# Titan_v1p3.net
KiCad netlist of a schematic drawn in EAGLE
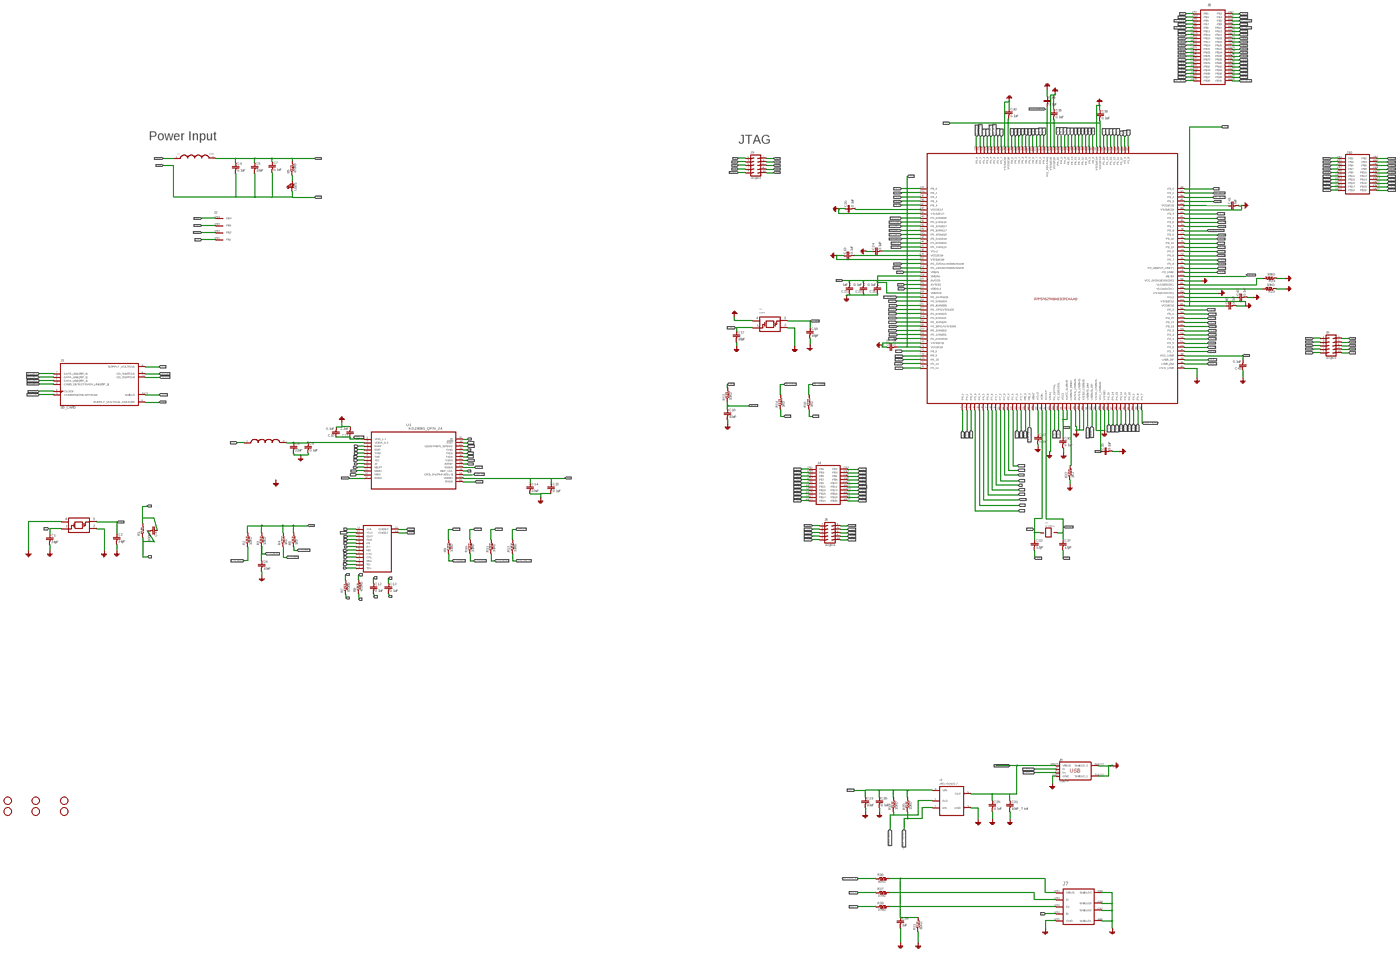
[diagram p0: schematic, sheet 1, overview]
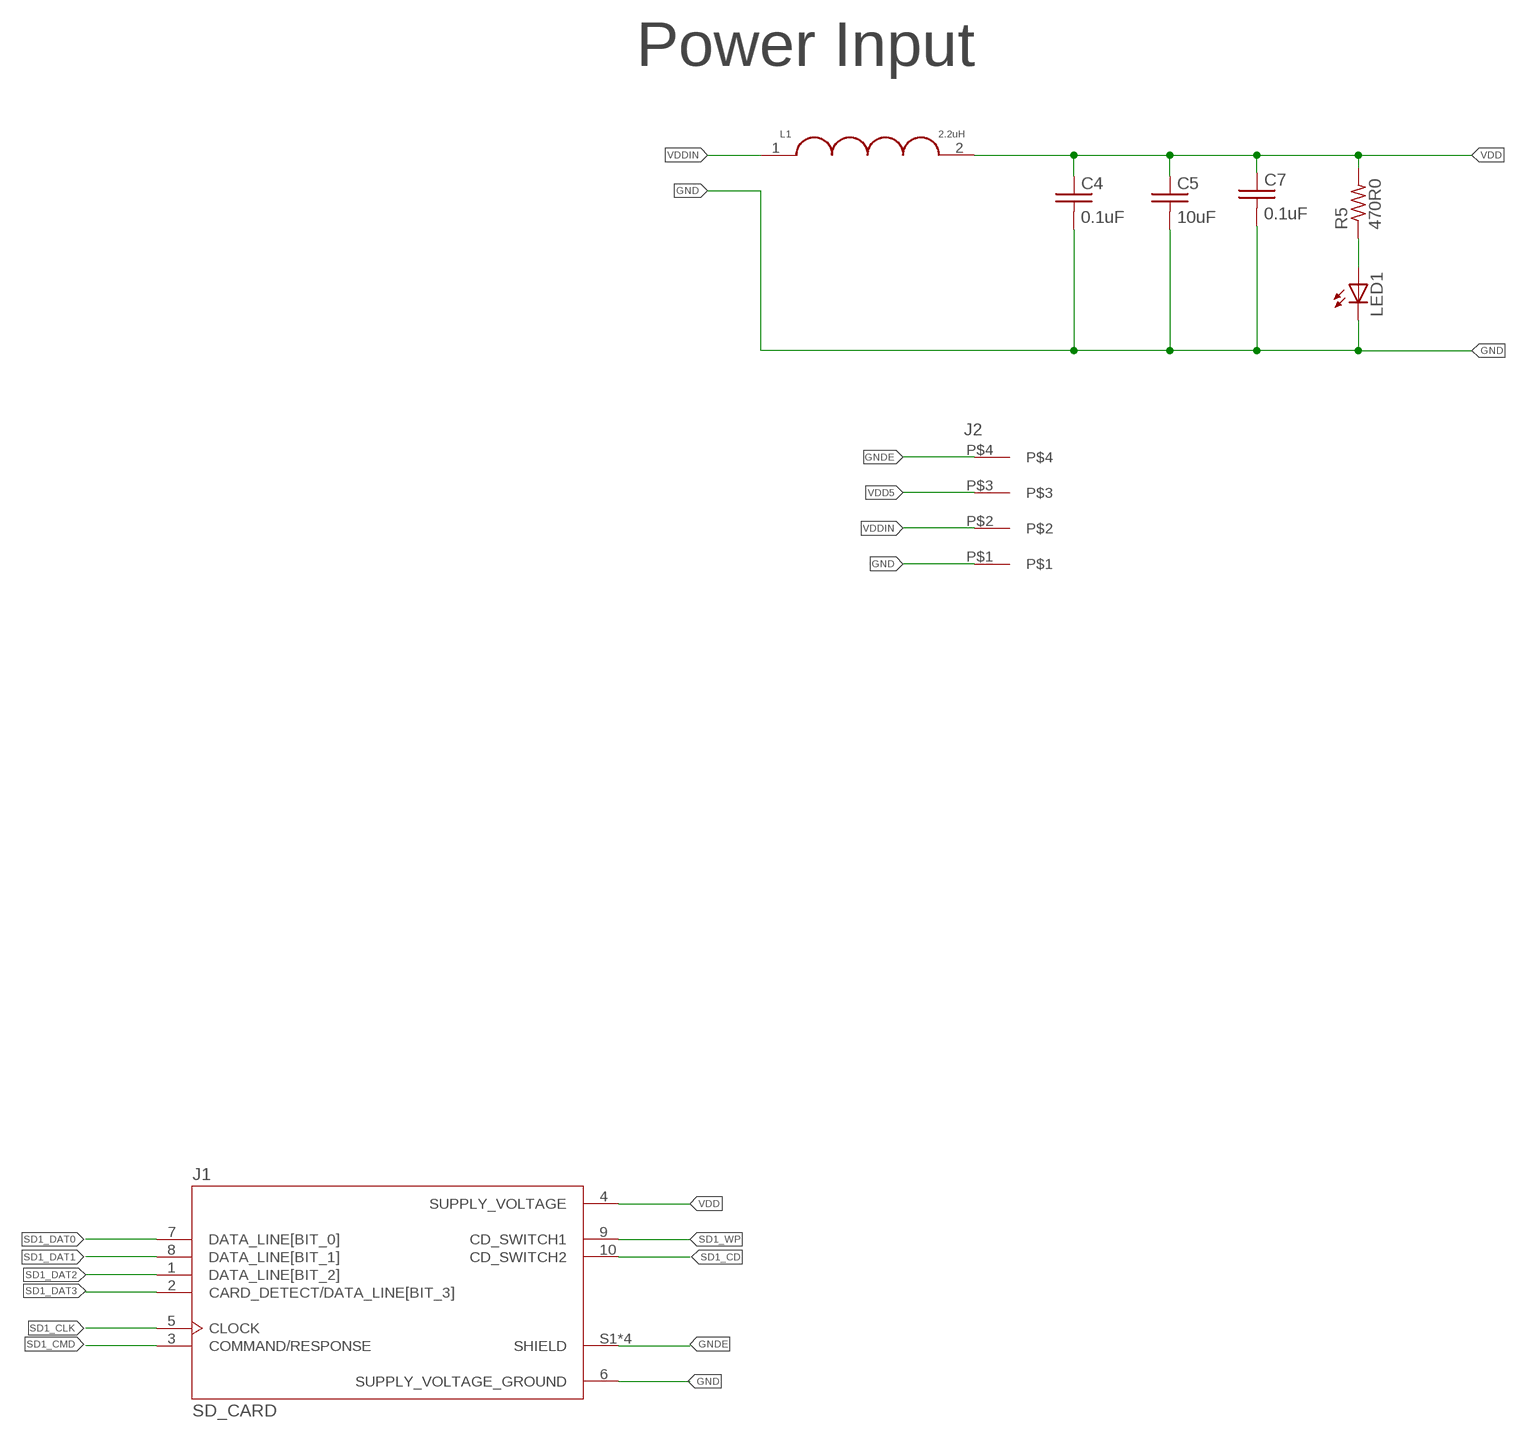
[diagram p1: schematic, sheet 1, part 1 of 5]
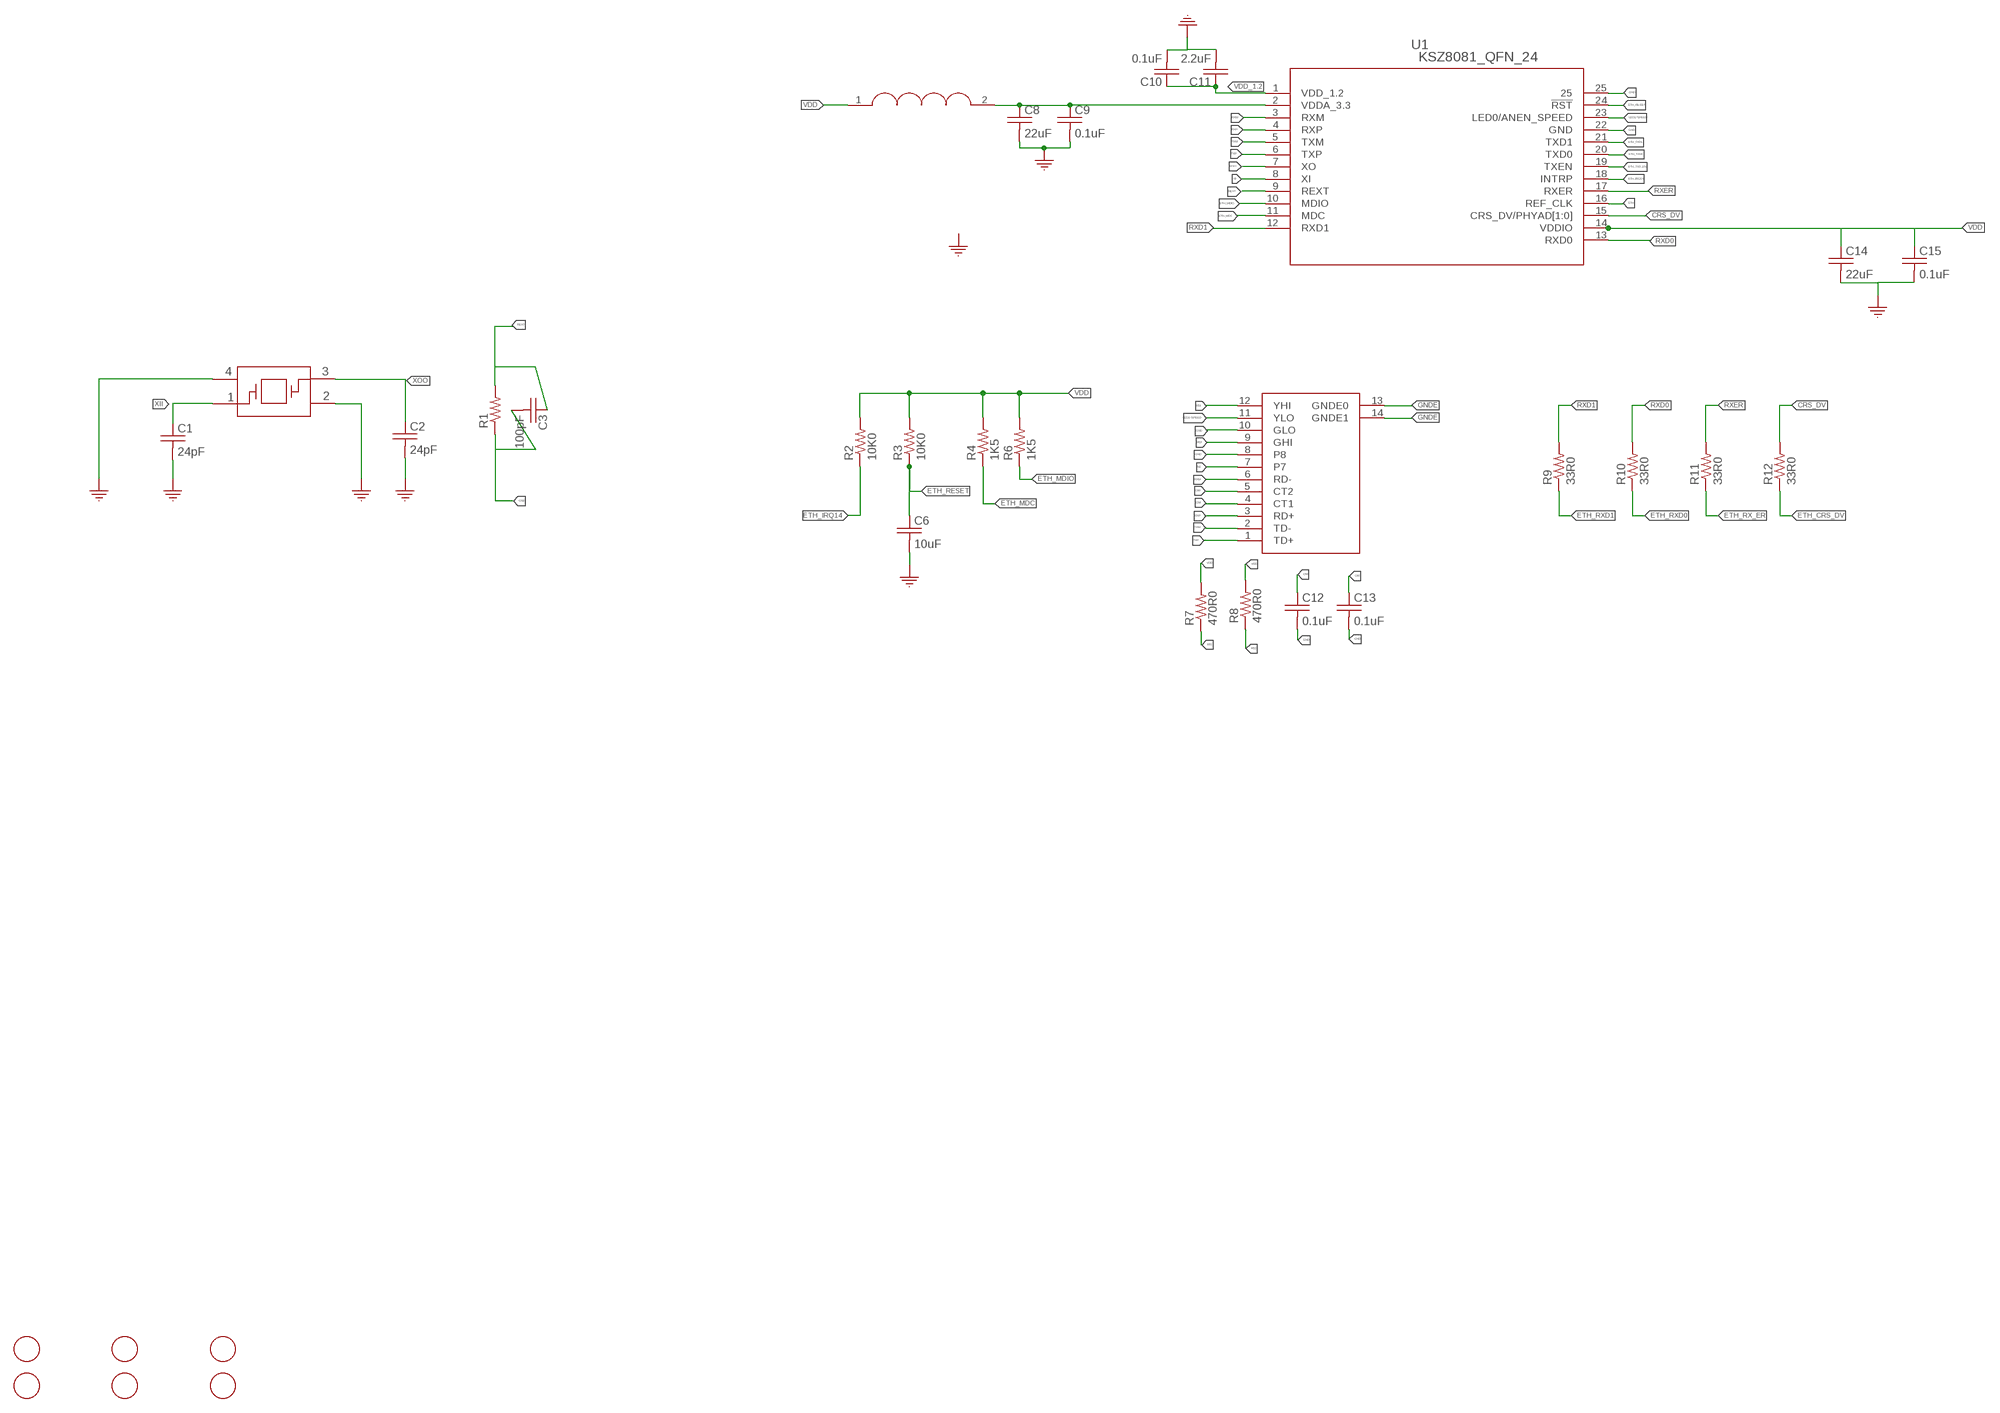
[diagram p2: schematic, sheet 1, part 2 of 5]
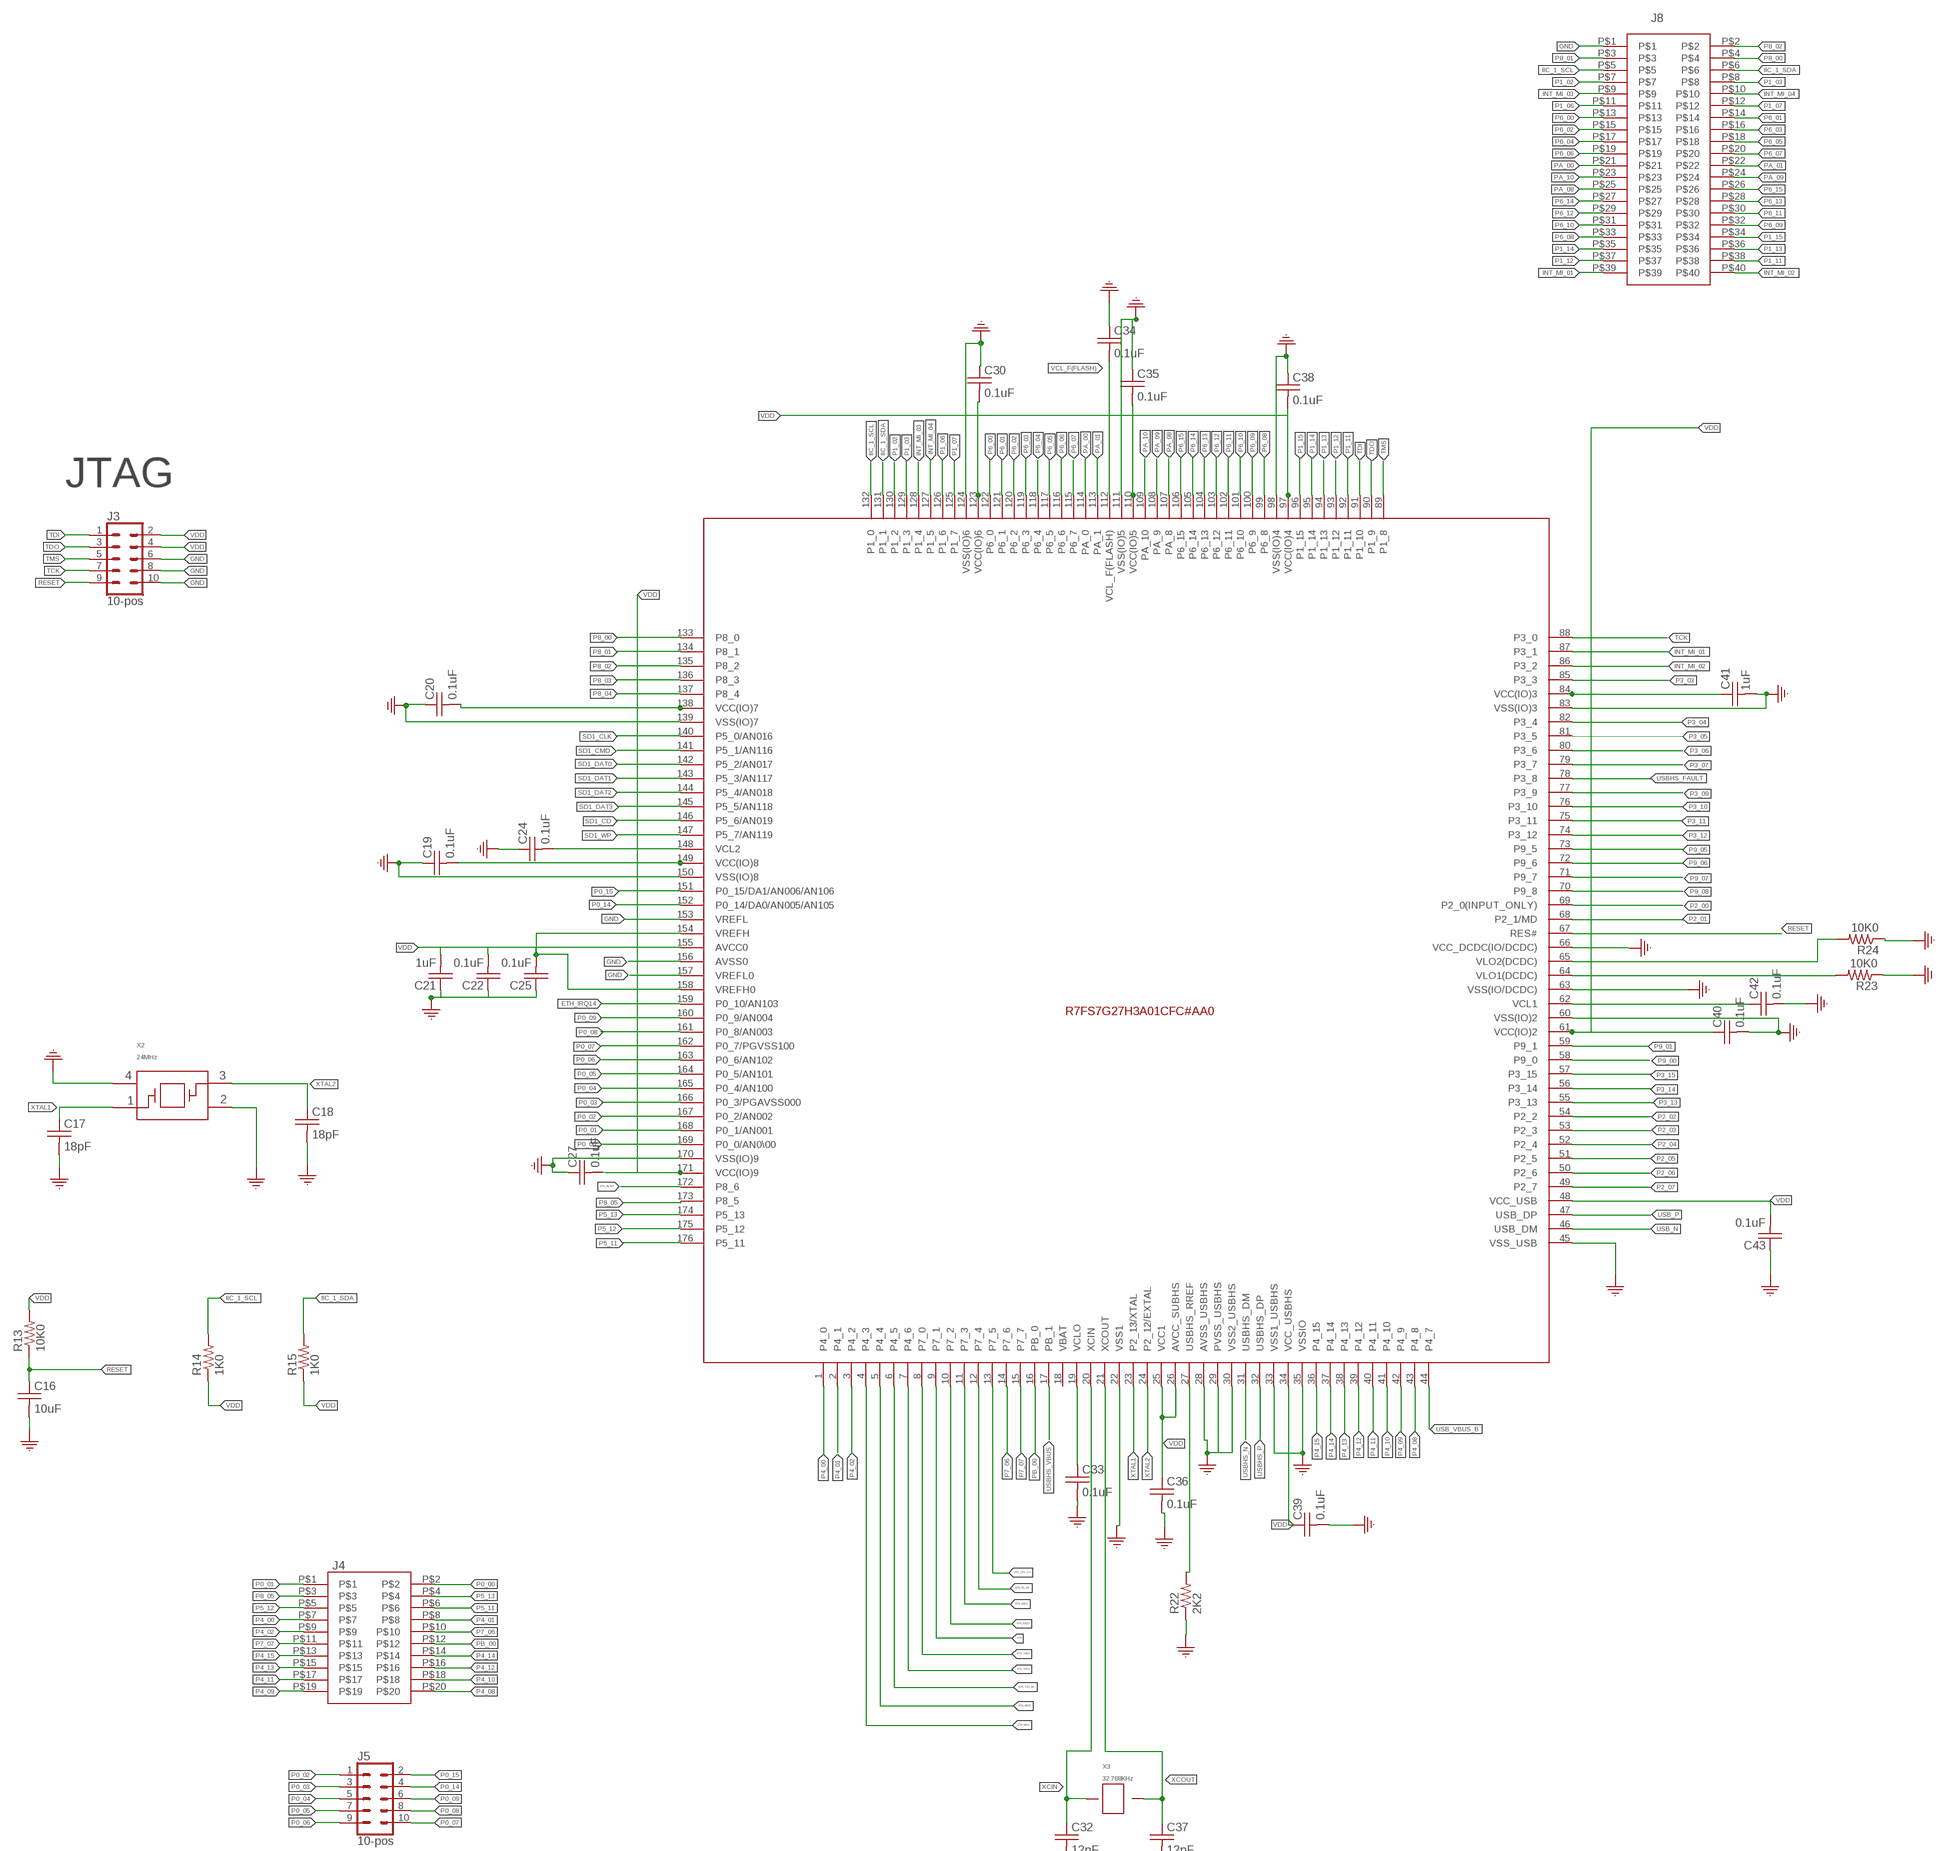
[diagram p3: schematic, sheet 1, part 3 of 5]
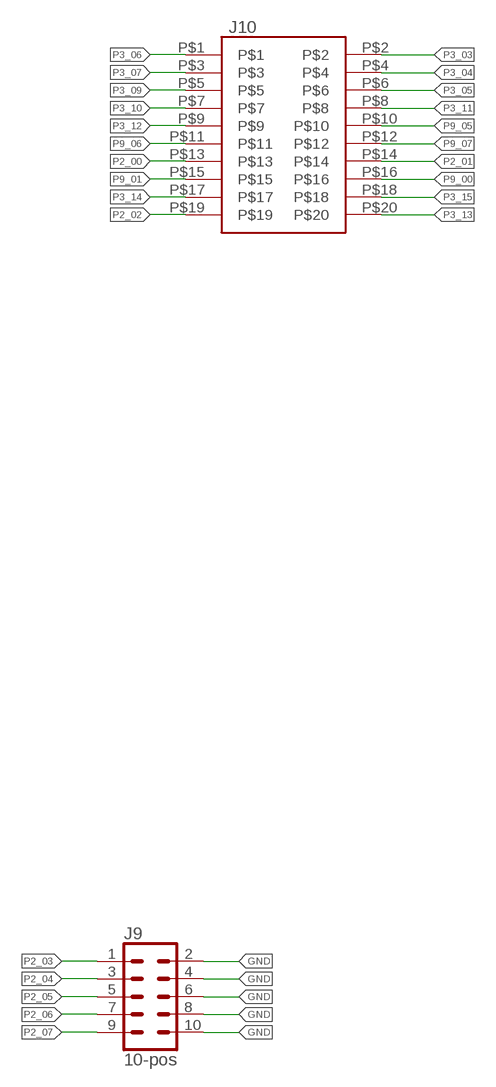
[diagram p4: schematic, sheet 1, part 4 of 5]
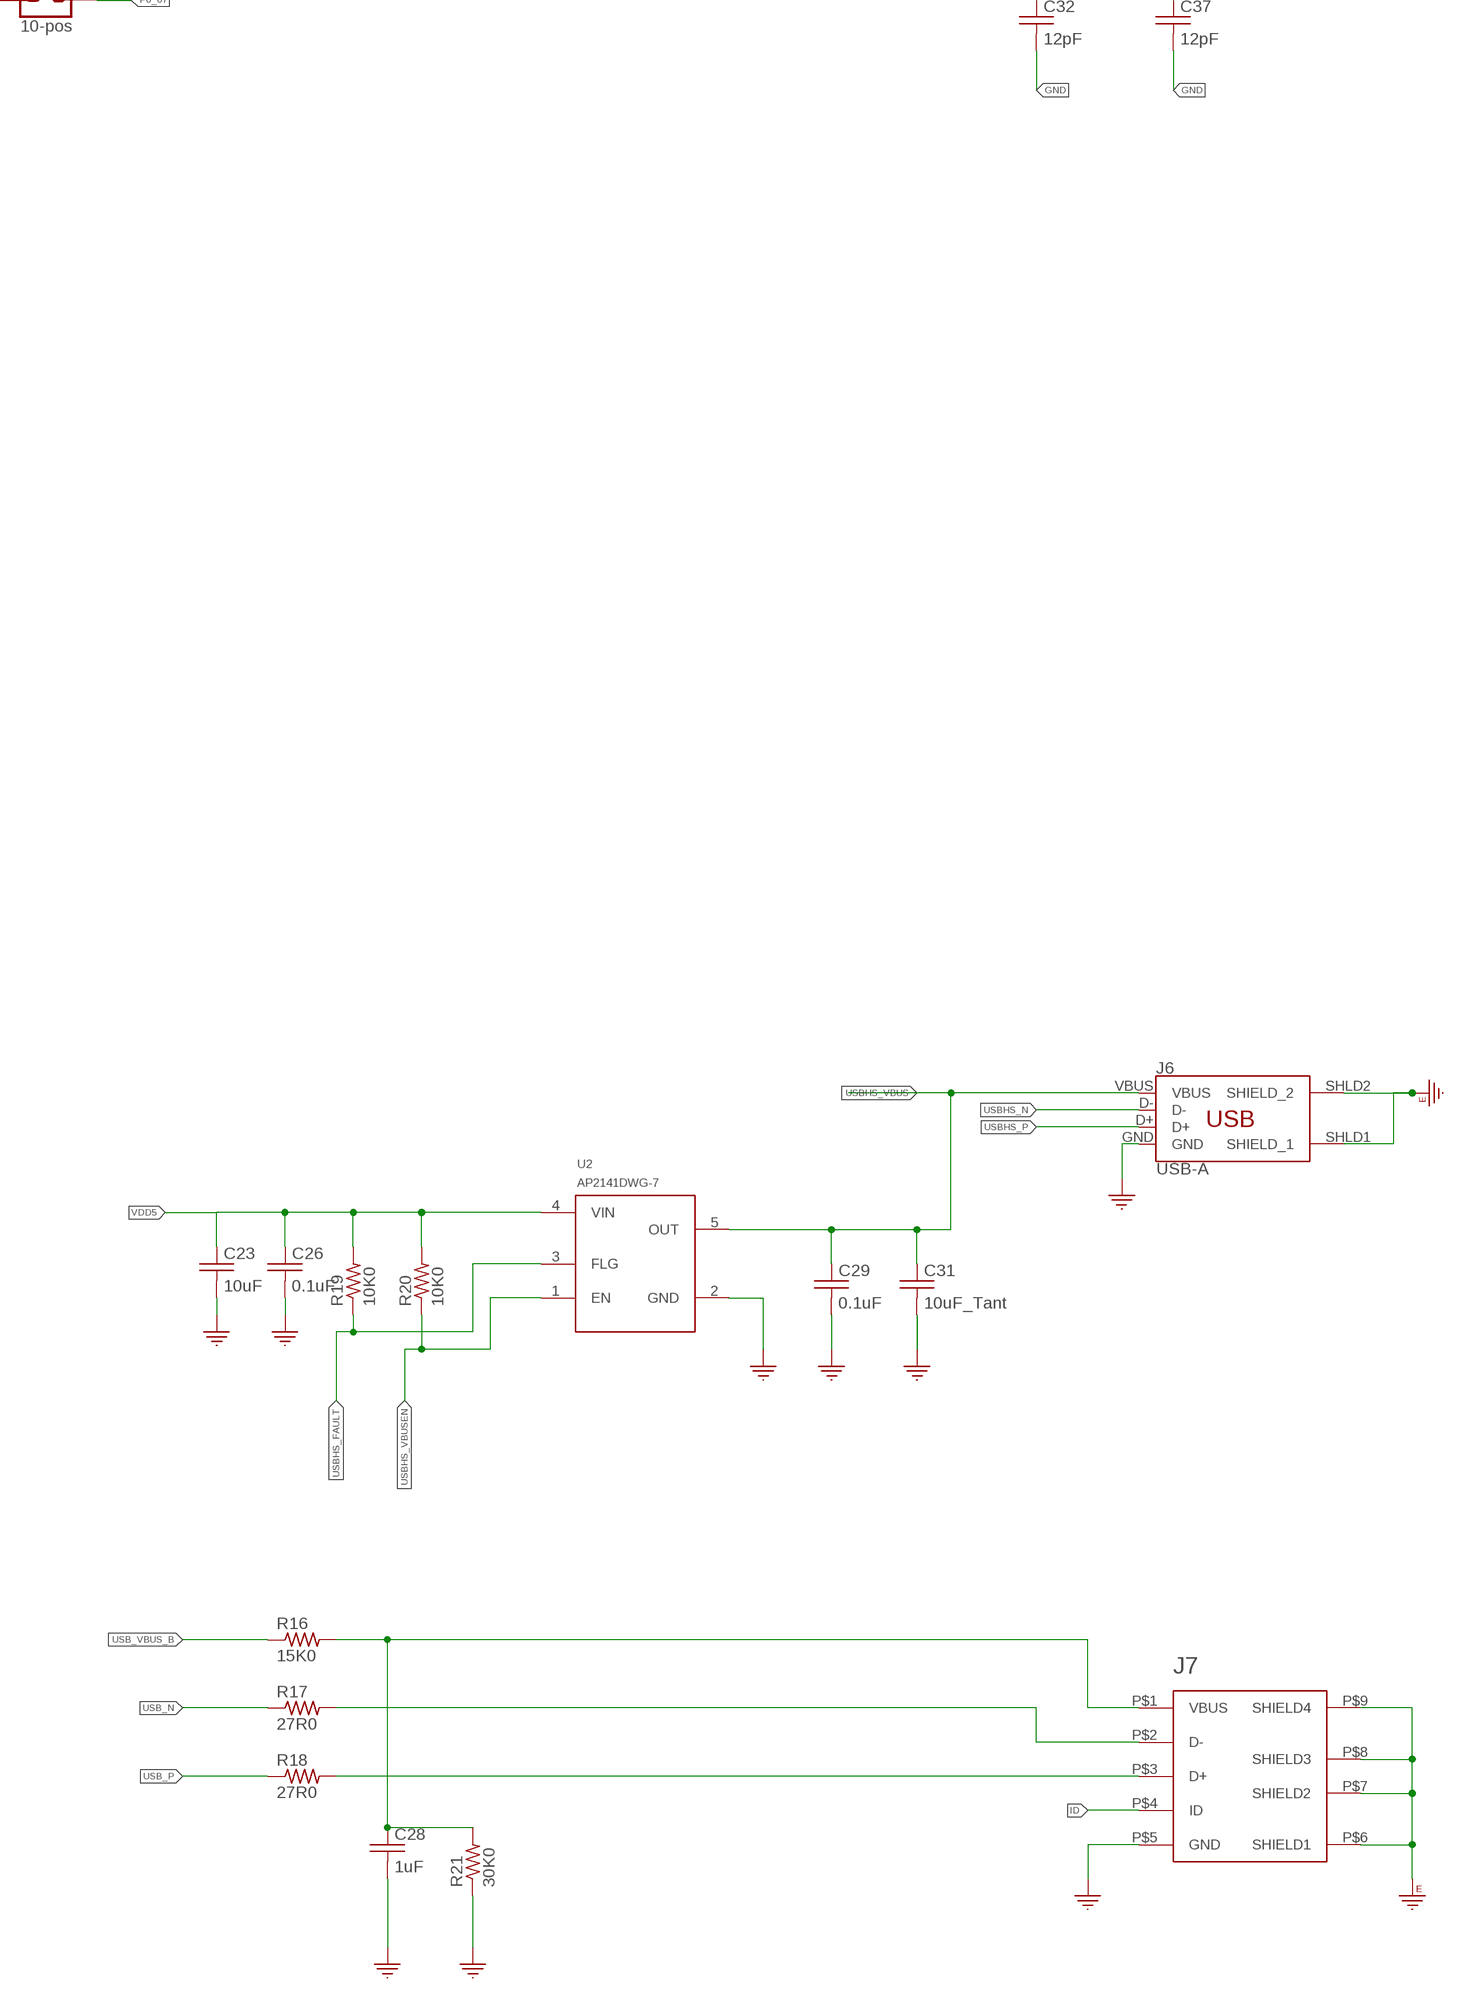
[diagram p5: schematic, sheet 1, part 5 of 5]

(export (version "E")
  (design (tool "Eeschema 10.0.6"))
  (components
    (comp (ref "C1")
      (value "24pF")
      (footprint "eagle-import:0402")
      (fields (field (name "PARTNO") "CC0402GRNPO9BN240"))
      (libsource (lib "eagle-import") (part "C_0402_24PF"))
    )
    (comp (ref "C2")
      (value "24pF")
      (footprint "eagle-import:0402")
      (fields (field (name "PARTNO") "CC0402GRNPO9BN240"))
      (libsource (lib "eagle-import") (part "C_0402_24PF"))
    )
    (comp (ref "C3")
      (value "100pF")
      (footprint "eagle-import:0402")
      (fields (field (name "PARTNO") "CL05C101JB5NNNC"))
      (libsource (lib "eagle-import") (part "C_0402_100PF"))
    )
    (comp (ref "C4")
      (value "0.1uF")
      (footprint "eagle-import:0402")
      (fields (field (name "PARTNO") "CL05F104ZO5NNNC"))
      (libsource (lib "eagle-import") (part "C_0402_0.1UF"))
    )
    (comp (ref "C5")
      (value "10uF")
      (footprint "eagle-import:0402")
      (fields (field (name "PARTNO") "CL05A106MP8NUB8"))
      (libsource (lib "eagle-import") (part "C_0402_10UF"))
    )
    (comp (ref "C6")
      (value "10uF")
      (footprint "eagle-import:0402")
      (fields (field (name "PARTNO") "CL05A106MP8NUB8"))
      (libsource (lib "eagle-import") (part "C_0402_10UF"))
    )
    (comp (ref "C7")
      (value "0.1uF")
      (footprint "eagle-import:0402")
      (fields (field (name "PARTNO") "CL05F104ZO5NNNC"))
      (libsource (lib "eagle-import") (part "C_0402_0.1UF"))
    )
    (comp (ref "C8")
      (value "22uF")
      (footprint "eagle-import:0402")
      (fields (field (name "PARTNO") "CL05A226MQ5N6J8"))
      (libsource (lib "eagle-import") (part "C_0402_22UF"))
    )
    (comp (ref "C9")
      (value "0.1uF")
      (footprint "eagle-import:0402")
      (fields (field (name "PARTNO") "CL05F104ZO5NNNC"))
      (libsource (lib "eagle-import") (part "C_0402_0.1UF"))
    )
    (comp (ref "C10")
      (value "0.1uF")
      (footprint "eagle-import:0402")
      (fields (field (name "PARTNO") "CL05F104ZO5NNNC"))
      (libsource (lib "eagle-import") (part "C_0402_0.1UF"))
    )
    (comp (ref "C11")
      (value "2.2uF")
      (footprint "eagle-import:0402")
      (fields (field (name "PARTNO") "GRM155C81C225ME15D"))
      (libsource (lib "eagle-import") (part "C_0402_2.2UF"))
    )
    (comp (ref "C12")
      (value "0.1uF")
      (footprint "eagle-import:0402")
      (fields (field (name "PARTNO") "CL05F104ZO5NNNC"))
      (libsource (lib "eagle-import") (part "C_0402_0.1UF"))
    )
    (comp (ref "C13")
      (value "0.1uF")
      (footprint "eagle-import:0402")
      (fields (field (name "PARTNO") "CL05F104ZO5NNNC"))
      (libsource (lib "eagle-import") (part "C_0402_0.1UF"))
    )
    (comp (ref "C14")
      (value "22uF")
      (footprint "eagle-import:0402")
      (fields (field (name "PARTNO") "CL05A226MQ5N6J8"))
      (libsource (lib "eagle-import") (part "C_0402_22UF"))
    )
    (comp (ref "C15")
      (value "0.1uF")
      (footprint "eagle-import:0402")
      (fields (field (name "PARTNO") "CL05F104ZO5NNNC"))
      (libsource (lib "eagle-import") (part "C_0402_0.1UF"))
    )
    (comp (ref "C16")
      (value "10uF")
      (footprint "eagle-import:0402")
      (fields (field (name "PARTNO") "CL05A106MP8NUB8"))
      (libsource (lib "eagle-import") (part "C_0402_10UF"))
    )
    (comp (ref "C17")
      (value "18pF")
      (footprint "eagle-import:0402")
      (fields (field (name "PARTNO") "UMK105CG180JV-F"))
      (libsource (lib "eagle-import") (part "C_0402_18PF"))
    )
    (comp (ref "C18")
      (value "18pF")
      (footprint "eagle-import:0402")
      (fields (field (name "PARTNO") "UMK105CG180JV-F"))
      (libsource (lib "eagle-import") (part "C_0402_18PF"))
    )
    (comp (ref "C19")
      (value "0.1uF")
      (footprint "eagle-import:0402")
      (fields (field (name "PARTNO") "CL05F104ZO5NNNC"))
      (libsource (lib "eagle-import") (part "C_0402_0.1UF"))
    )
    (comp (ref "C20")
      (value "0.1uF")
      (footprint "eagle-import:0402")
      (fields (field (name "PARTNO") "CL05F104ZO5NNNC"))
      (libsource (lib "eagle-import") (part "C_0402_0.1UF"))
    )
    (comp (ref "C21")
      (value "1uF")
      (footprint "eagle-import:0402")
      (fields (field (name "PARTNO") "CL05A105KO5NNNC"))
      (libsource (lib "eagle-import") (part "C_0402_1UF"))
    )
    (comp (ref "C22")
      (value "0.1uF")
      (footprint "eagle-import:0402")
      (fields (field (name "PARTNO") "CL05F104ZO5NNNC"))
      (libsource (lib "eagle-import") (part "C_0402_0.1UF"))
    )
    (comp (ref "C23")
      (value "10uF")
      (footprint "eagle-import:0402")
      (fields (field (name "PARTNO") "CL05A106MP8NUB8"))
      (libsource (lib "eagle-import") (part "C_0402_10UF"))
    )
    (comp (ref "C24")
      (value "0.1uF")
      (footprint "eagle-import:0402")
      (fields (field (name "PARTNO") "CL05F104ZO5NNNC"))
      (libsource (lib "eagle-import") (part "C_0402_0.1UF"))
    )
    (comp (ref "C25")
      (value "0.1uF")
      (footprint "eagle-import:0402")
      (fields (field (name "PARTNO") "CL05F104ZO5NNNC"))
      (libsource (lib "eagle-import") (part "C_0402_0.1UF"))
    )
    (comp (ref "C26")
      (value "0.1uF")
      (footprint "eagle-import:0402")
      (fields (field (name "PARTNO") "CL05F104ZO5NNNC"))
      (libsource (lib "eagle-import") (part "C_0402_0.1UF"))
    )
    (comp (ref "C27")
      (value "0.1uF")
      (footprint "eagle-import:0402")
      (fields (field (name "PARTNO") "CL05F104ZO5NNNC"))
      (libsource (lib "eagle-import") (part "C_0402_0.1UF"))
    )
    (comp (ref "C28")
      (value "1uF")
      (footprint "eagle-import:0402")
      (fields (field (name "PARTNO") "CL05A105KO5NNNC"))
      (libsource (lib "eagle-import") (part "C_0402_1UF"))
    )
    (comp (ref "C29")
      (value "0.1uF")
      (footprint "eagle-import:0402")
      (fields (field (name "PARTNO") "CL05F104ZO5NNNC"))
      (libsource (lib "eagle-import") (part "C_0402_0.1UF"))
    )
    (comp (ref "C30")
      (value "0.1uF")
      (footprint "eagle-import:0402")
      (fields (field (name "PARTNO") "CL05F104ZO5NNNC"))
      (libsource (lib "eagle-import") (part "C_0402_0.1UF"))
    )
    (comp (ref "C31")
      (value "10uF_Tant")
      (footprint "eagle-import:C1210")
      (fields (field (name "PARTNO") "TPST106K016H0800"))
      (libsource (lib "eagle-import") (part "C_1210_10UF_TANT"))
    )
    (comp (ref "C32")
      (value "12pF")
      (footprint "eagle-import:0402")
      (fields (field (name "PARTNO") "CL05C120JB5NNNC"))
      (libsource (lib "eagle-import") (part "C_0402_12PF"))
    )
    (comp (ref "C33")
      (value "0.1uF")
      (footprint "eagle-import:0402")
      (fields (field (name "PARTNO") "CL05F104ZO5NNNC"))
      (libsource (lib "eagle-import") (part "C_0402_0.1UF"))
    )
    (comp (ref "C34")
      (value "0.1uF")
      (footprint "eagle-import:0402")
      (fields (field (name "PARTNO") "CL05F104ZO5NNNC"))
      (libsource (lib "eagle-import") (part "C_0402_0.1UF"))
    )
    (comp (ref "C35")
      (value "0.1uF")
      (footprint "eagle-import:0402")
      (fields (field (name "PARTNO") "CL05F104ZO5NNNC"))
      (libsource (lib "eagle-import") (part "C_0402_0.1UF"))
    )
    (comp (ref "C36")
      (value "0.1uF")
      (footprint "eagle-import:0402")
      (fields (field (name "PARTNO") "CL05F104ZO5NNNC"))
      (libsource (lib "eagle-import") (part "C_0402_0.1UF"))
    )
    (comp (ref "C37")
      (value "12pF")
      (footprint "eagle-import:0402")
      (fields (field (name "PARTNO") "CL05C120JB5NNNC"))
      (libsource (lib "eagle-import") (part "C_0402_12PF"))
    )
    (comp (ref "C38")
      (value "0.1uF")
      (footprint "eagle-import:0402")
      (fields (field (name "PARTNO") "CL05F104ZO5NNNC"))
      (libsource (lib "eagle-import") (part "C_0402_0.1UF"))
    )
    (comp (ref "C39")
      (value "0.1uF")
      (footprint "eagle-import:0402")
      (fields (field (name "PARTNO") "CL05F104ZO5NNNC"))
      (libsource (lib "eagle-import") (part "C_0402_0.1UF"))
    )
    (comp (ref "C40")
      (value "0.1uF")
      (footprint "eagle-import:0402")
      (fields (field (name "PARTNO") "CL05F104ZO5NNNC"))
      (libsource (lib "eagle-import") (part "C_0402_0.1UF"))
    )
    (comp (ref "C41")
      (value "1uF")
      (footprint "eagle-import:0402")
      (fields (field (name "PARTNO") "CL05A105KO5NNNC"))
      (libsource (lib "eagle-import") (part "C_0402_1UF"))
    )
    (comp (ref "C42")
      (value "0.1uF")
      (footprint "eagle-import:0402")
      (fields (field (name "PARTNO") "CL05F104ZO5NNNC"))
      (libsource (lib "eagle-import") (part "C_0402_0.1UF"))
    )
    (comp (ref "C43")
      (value "0.1uF")
      (footprint "eagle-import:0402")
      (fields (field (name "PARTNO") "CL05F104ZO5NNNC"))
      (libsource (lib "eagle-import") (part "C_0402_0.1UF"))
    )
    (comp (ref "FB1")
      (value "FB2_603")
      (footprint "eagle-import:0603")
      (fields (field (name "PARTNO") "BLM18PG121SN1D"))
      (libsource (lib "eagle-import") (part "FB_0603_120_OHM0603"))
    )
    (comp (ref "J1")
      (value "SD_CARD")
      (footprint "eagle-import:SD_CARD")
      (fields (field (name "MF") "Amphenol ICC") (field (name "PARTNO") "114-00841-68"))
      (libsource (lib "eagle-import") (part "SD_CARD_1140084168"))
    )
    (comp (ref "J2")
      (value "4-pos")
      (footprint "eagle-import:1X4_3.81MM_PITCH")
      (fields (field (name "PARTNO") "691322310004"))
      (libsource (lib "eagle-import") (part "3.81MM_1_X_4_RT_ANGLE_PLUG_HEADER"))
    )
    (comp (ref "J3")
      (value "10-pos")
      (footprint "eagle-import:2X5")
      (fields (field (name "PARTNO") "PH2RA-10-UA"))
      (libsource (lib "eagle-import") (part "CONN_05X2_RAPTH"))
    )
    (comp (ref "J4")
      (value "20-pos")
      (footprint "eagle-import:2_X_10_.1_INCH")
      (fields (field (name "PARTNO") "67996-420HLF"))
      (libsource (lib "eagle-import") (part "2_X_10_HEADER_GENERIC"))
    )
    (comp (ref "J5")
      (value "10-pos")
      (footprint "eagle-import:2X5")
      (fields (field (name "PARTNO") "PH2RA-10-UA"))
      (libsource (lib "eagle-import") (part "CONN_05X2_RAPTH"))
    )
    (comp (ref "J6")
      (value "USB-A")
      (footprint "eagle-import:USB_A_SMT")
      (fields (field (name "PARTNO") "87583-3010RPALF"))
      (libsource (lib "eagle-import") (part "USB_A"))
    )
    (comp (ref "J7")
      (value "USB-B-Micro")
      (footprint "eagle-import:USB_MICRO-B")
      (fields (field (name "PARTNO") "10118192-0002LF"))
      (libsource (lib "eagle-import") (part "USB_MICRO-B"))
    )
    (comp (ref "J8")
      (value "40-pos")
      (footprint "eagle-import:HEADER_2_X_20_.1_INCH")
      (fields (field (name "PARTNO") "61304021021"))
      (libsource (lib "eagle-import") (part "HEADER_2_X_20_GENERIC"))
    )
    (comp (ref "J9")
      (value "10-pos")
      (footprint "eagle-import:2X5")
      (fields (field (name "PARTNO") "PH2RA-10-UA"))
      (libsource (lib "eagle-import") (part "CONN_05X2_RAPTH"))
    )
    (comp (ref "J10")
      (value "20-pos")
      (footprint "eagle-import:2_X_10_.1_INCH")
      (fields (field (name "PARTNO") "67996-420HLF"))
      (libsource (lib "eagle-import") (part "2_X_10_HEADER_GENERIC"))
    )
    (comp (ref "L1")
      (value "2.2uH")
      (footprint "eagle-import:1008")
      (fields (field (name "PARTNO") "LQM2HPN2R2MG0L"))
      (libsource (lib "eagle-import") (part "INDUCTOR_1008_2.2_MH_1.3A"))
    )
    (comp (ref "LED1")
      (value "Green")
      (footprint "eagle-import:0805")
      (fields (field (name "PARTNO") "LG R971-KN-1"))
      (libsource (lib "eagle-import") (part "LED_0805_GREEN"))
    )
    (comp (ref "R1")
      (value "6K49")
      (footprint "eagle-import:0402")
      (fields (field (name "PARTNO") "RMCF0402FT6K49"))
      (libsource (lib "eagle-import") (part "R_0402_6K49"))
    )
    (comp (ref "R2")
      (value "10K0")
      (footprint "eagle-import:0402")
      (fields (field (name "PARTNO") "RMCF0402JT10K0"))
      (libsource (lib "eagle-import") (part "R_0402_10K0"))
    )
    (comp (ref "R3")
      (value "10K0")
      (footprint "eagle-import:0402")
      (fields (field (name "PARTNO") "RMCF0402JT10K0"))
      (libsource (lib "eagle-import") (part "R_0402_10K0"))
    )
    (comp (ref "R4")
      (value "1K5")
      (footprint "eagle-import:0402")
      (fields (field (name "PARTNO") "RMCF0402JT1K50"))
      (libsource (lib "eagle-import") (part "R_0402_1K5"))
    )
    (comp (ref "R5")
      (value "470R0")
      (footprint "eagle-import:0402")
      (fields (field (name "PARTNO") "RMCF0402JT470R"))
      (libsource (lib "eagle-import") (part "R_0402_470R0"))
    )
    (comp (ref "R6")
      (value "1K5")
      (footprint "eagle-import:0402")
      (fields (field (name "PARTNO") "RMCF0402JT1K50"))
      (libsource (lib "eagle-import") (part "R_0402_1K5"))
    )
    (comp (ref "R7")
      (value "470R0")
      (footprint "eagle-import:0402")
      (fields (field (name "PARTNO") "RMCF0402JT470R"))
      (libsource (lib "eagle-import") (part "R_0402_470R0"))
    )
    (comp (ref "R8")
      (value "470R0")
      (footprint "eagle-import:0402")
      (fields (field (name "PARTNO") "RMCF0402JT470R"))
      (libsource (lib "eagle-import") (part "R_0402_470R0"))
    )
    (comp (ref "R9")
      (value "33R0")
      (footprint "eagle-import:0402")
      (fields (field (name "PARTNO") "RMCF0402JT33R0"))
      (libsource (lib "eagle-import") (part "R_0402_33R0"))
    )
    (comp (ref "R10")
      (value "33R0")
      (footprint "eagle-import:0402")
      (fields (field (name "PARTNO") "RMCF0402JT33R0"))
      (libsource (lib "eagle-import") (part "R_0402_33R0"))
    )
    (comp (ref "R11")
      (value "33R0")
      (footprint "eagle-import:0402")
      (fields (field (name "PARTNO") "RMCF0402JT33R0"))
      (libsource (lib "eagle-import") (part "R_0402_33R0"))
    )
    (comp (ref "R12")
      (value "33R0")
      (footprint "eagle-import:0402")
      (fields (field (name "PARTNO") "RMCF0402JT33R0"))
      (libsource (lib "eagle-import") (part "R_0402_33R0"))
    )
    (comp (ref "R13")
      (value "10K0")
      (footprint "eagle-import:0402")
      (fields (field (name "PARTNO") "RMCF0402JT10K0"))
      (libsource (lib "eagle-import") (part "R_0402_10K0"))
    )
    (comp (ref "R14")
      (value "1K0")
      (footprint "eagle-import:0402")
      (fields (field (name "PARTNO") "CRG0402J1K0"))
      (libsource (lib "eagle-import") (part "R_0402_1K0"))
    )
    (comp (ref "R15")
      (value "1K0")
      (footprint "eagle-import:0402")
      (fields (field (name "PARTNO") "CRG0402J1K0"))
      (libsource (lib "eagle-import") (part "R_0402_1K0"))
    )
    (comp (ref "R16")
      (value "15K0")
      (footprint "eagle-import:0402")
      (fields (field (name "PARTNO") "RMCF0402JT15K0"))
      (libsource (lib "eagle-import") (part "R_0402_15K0"))
    )
    (comp (ref "R17")
      (value "27R0")
      (footprint "eagle-import:0402")
      (fields (field (name "PARTNO") "RMCF0402JT27R0"))
      (libsource (lib "eagle-import") (part "R_0402_27R0"))
    )
    (comp (ref "R18")
      (value "27R0")
      (footprint "eagle-import:0402")
      (fields (field (name "PARTNO") "RMCF0402JT27R0"))
      (libsource (lib "eagle-import") (part "R_0402_27R0"))
    )
    (comp (ref "R19")
      (value "10K0")
      (footprint "eagle-import:0402")
      (fields (field (name "PARTNO") "RMCF0402JT10K0"))
      (libsource (lib "eagle-import") (part "R_0402_10K0"))
    )
    (comp (ref "R20")
      (value "10K0")
      (footprint "eagle-import:0402")
      (fields (field (name "PARTNO") "RMCF0402JT10K0"))
      (libsource (lib "eagle-import") (part "R_0402_10K0"))
    )
    (comp (ref "R21")
      (value "30K0")
      (footprint "eagle-import:0402")
      (fields (field (name "PARTNO") "RC0402JR-0730KL"))
      (libsource (lib "eagle-import") (part "R_0402_30K0"))
    )
    (comp (ref "R22")
      (value "2K2")
      (footprint "eagle-import:0402")
      (fields (field (name "PARTNO") "RMCF0402JT2K20"))
      (libsource (lib "eagle-import") (part "R_0402_2K2"))
    )
    (comp (ref "R23")
      (value "10K0")
      (footprint "eagle-import:0402")
      (fields (field (name "PARTNO") "RMCF0402JT10K0"))
      (libsource (lib "eagle-import") (part "R_0402_10K0"))
    )
    (comp (ref "R24")
      (value "10K0")
      (footprint "eagle-import:0402")
      (fields (field (name "PARTNO") "RMCF0402JT10K0"))
      (libsource (lib "eagle-import") (part "R_0402_10K0"))
    )
    (comp (ref "RJ1")
      (value "RJ45")
      (footprint "eagle-import:RJ45_TH_ELEC")
      (fields (field (name "PARTNO") "13F-64GYD2PL2NL"))
      (libsource (lib "eagle-import") (part "RJ45_WITH_ELEC"))
    )
    (comp (ref "U$1")
      (value "FIDUCIAL_1MM")
      (footprint "eagle-import:FIDUCIAL_1MM")
      (libsource (lib "eagle-import") (part "FIDUCIAL_1MM"))
    )
    (comp (ref "U$2")
      (value "FIDUCIAL_1MM")
      (footprint "eagle-import:FIDUCIAL_1MM")
      (libsource (lib "eagle-import") (part "FIDUCIAL_1MM"))
    )
    (comp (ref "U$3")
      (value "FIDUCIAL_1MM")
      (footprint "eagle-import:FIDUCIAL_1MM")
      (libsource (lib "eagle-import") (part "FIDUCIAL_1MM"))
    )
    (comp (ref "U$4")
      (value "FIDUCIAL_1MM")
      (footprint "eagle-import:FIDUCIAL_1MM")
      (libsource (lib "eagle-import") (part "FIDUCIAL_1MM"))
    )
    (comp (ref "U$5")
      (value "FIDUCIAL_1MM")
      (footprint "eagle-import:FIDUCIAL_1MM")
      (libsource (lib "eagle-import") (part "FIDUCIAL_1MM"))
    )
    (comp (ref "U$6")
      (value "FIDUCIAL_1MM")
      (footprint "eagle-import:FIDUCIAL_1MM")
      (libsource (lib "eagle-import") (part "FIDUCIAL_1MM"))
    )
    (comp (ref "U1")
      (value "KSZ8081_QFN_24")
      (footprint "eagle-import:QFN-24-M")
      (fields (field (name "PARTNO") "KSZ8081RNACA"))
      (libsource (lib "eagle-import") (part "KSZ8081RNACAQFN-24-M"))
    )
    (comp (ref "U2")
      (value "AP2151DWG-7")
      (footprint "eagle-import:SOT-23-5")
      (fields (field (name "PARTNO") "AP2151WG-7"))
      (libsource (lib "eagle-import") (part "AP2151DWG-7"))
    )
    (comp (ref "U3")
      (value "S7G2LQFP176")
      (footprint "eagle-import:LQFP176_24X24")
      (fields (field (name "PARTNO") "R7FS7G27H3A01CFC#AA0"))
      (libsource (lib "eagle-import") (part "S7G2_X_176"))
    )
    (comp (ref "X1")
      (value "25MHz")
      (footprint "eagle-import:SMD_3225")
      (fields (field (name "PARTNO") "FA-238 25.0000MB-B3"))
      (libsource (lib "eagle-import") (part "XTAL_25_MHZ"))
    )
    (comp (ref "X2")
      (value "24MHz")
      (footprint "eagle-import:SMD_3225")
      (fields (field (name "PARTNO") "FA-238 24.0000MB-C3 "))
      (libsource (lib "eagle-import") (part "XTAL_24_MHZ"))
    )
    (comp (ref "X3")
      (value "32.768KHz")
      (footprint "eagle-import:SMD_X_2_PADS")
      (fields (field (name "PARTNO") "ABS07-32.768KHZ-T"))
      (libsource (lib "eagle-import") (part "XTAL_32.768KHZ"))
    )
  )
  (nets
    (net (code "1") (name "C58") (class "Default")
      (node (ref "C12") (pin "P$1") (pinfunction "1_P$1") (pintype "passive"))
      (node (ref "RJ1") (pin "4") (pinfunction "CT1_4") (pintype "bidirectional"))
    )
    (net (code "2") (name "C60") (class "Default")
      (node (ref "C13") (pin "P$1") (pinfunction "1_P$1") (pintype "passive"))
      (node (ref "RJ1") (pin "5") (pinfunction "CT2_5") (pintype "bidirectional"))
    )
    (net (code "3") (name "CRS_DV") (class "Default")
      (node (ref "R12") (pin "P$2") (pinfunction "2_P$2") (pintype "passive"))
      (node (ref "U1") (pin "15") (pinfunction "CRS_DV/PHYAD[1:0]_15") (pintype "bidirectional"))
    )
    (net (code "4") (name "ETH") (class "Default")
      (node (ref "U1") (pin "16") (pinfunction "REF_CLK_16") (pintype "bidirectional"))
      (node (ref "U3") (pin "9") (pinfunction "P7_1_9") (pintype "bidirectional"))
    )
    (net (code "5") (name "ETH_CRS_DV") (class "Default")
      (node (ref "R12") (pin "P$1") (pinfunction "1_P$1") (pintype "passive"))
      (node (ref "U3") (pin "13") (pinfunction "P7_5_13") (pintype "bidirectional"))
    )
    (net (code "6") (name "ETH_IRQ14") (class "Default")
      (node (ref "R2") (pin "P$1") (pinfunction "1_P$1") (pintype "passive"))
      (node (ref "U1") (pin "18") (pinfunction "INTRP_18") (pintype "bidirectional"))
      (node (ref "U3") (pin "159") (pinfunction "P0_10/AN103_159") (pintype "bidirectional"))
    )
    (net (code "7") (name "ETH_MDC") (class "Default")
      (node (ref "R4") (pin "P$1") (pinfunction "1_P$1") (pintype "passive"))
      (node (ref "U1") (pin "11") (pinfunction "MDC_11") (pintype "input"))
      (node (ref "U3") (pin "4") (pinfunction "P4_3_4") (pintype "bidirectional"))
    )
    (net (code "8") (name "ETH_MDIO") (class "Default")
      (node (ref "R6") (pin "P$1") (pinfunction "1_P$1") (pintype "passive"))
      (node (ref "U1") (pin "10") (pinfunction "MDIO_10") (pintype "bidirectional"))
      (node (ref "U3") (pin "5") (pinfunction "P4_4_5") (pintype "bidirectional"))
    )
    (net (code "9") (name "ETH_RESET") (class "Default")
      (node (ref "C6") (pin "P$1") (pinfunction "1_P$1") (pintype "passive"))
      (node (ref "R3") (pin "P$1") (pinfunction "1_P$1") (pintype "passive"))
      (node (ref "U1") (pin "24") (pinfunction "~{RST}_24") (pintype "input"))
      (node (ref "U3") (pin "172") (pinfunction "P8_6_172") (pintype "bidirectional"))
    )
    (net (code "10") (name "ETH_RXD0") (class "Default")
      (node (ref "R10") (pin "P$1") (pinfunction "1_P$1") (pintype "passive"))
      (node (ref "U3") (pin "10") (pinfunction "P7_2_10") (pintype "bidirectional"))
    )
    (net (code "11") (name "ETH_RXD1") (class "Default")
      (node (ref "R9") (pin "P$1") (pinfunction "1_P$1") (pintype "passive"))
      (node (ref "U3") (pin "11") (pinfunction "P7_3_11") (pintype "bidirectional"))
    )
    (net (code "12") (name "ETH_RX_ER") (class "Default")
      (node (ref "R11") (pin "P$1") (pinfunction "1_P$1") (pintype "passive"))
      (node (ref "U3") (pin "12") (pinfunction "P7_4_12") (pintype "bidirectional"))
    )
    (net (code "13") (name "ETH_TXD0") (class "Default")
      (node (ref "U1") (pin "20") (pinfunction "TXD0_20") (pintype "input"))
      (node (ref "U3") (pin "8") (pinfunction "P7_0_8") (pintype "bidirectional"))
    )
    (net (code "14") (name "ETH_TXD1") (class "Default")
      (node (ref "U1") (pin "21") (pinfunction "TXD1_21") (pintype "bidirectional"))
      (node (ref "U3") (pin "7") (pinfunction "P4_6_7") (pintype "bidirectional"))
    )
    (net (code "15") (name "ETH_TXD_EN") (class "Default")
      (node (ref "U1") (pin "19") (pinfunction "TXEN_19") (pintype "input"))
      (node (ref "U3") (pin "6") (pinfunction "P4_5_6") (pintype "bidirectional"))
    )
    (net (code "16") (name "GND") (class "Default")
      (node (ref "C1") (pin "P$2") (pinfunction "2_P$2") (pintype "passive"))
      (node (ref "C10") (pin "P$2") (pinfunction "2_P$2") (pintype "passive"))
      (node (ref "C11") (pin "P$2") (pinfunction "2_P$2") (pintype "passive"))
      (node (ref "C12") (pin "P$2") (pinfunction "2_P$2") (pintype "passive"))
      (node (ref "C13") (pin "P$2") (pinfunction "2_P$2") (pintype "passive"))
      (node (ref "C14") (pin "P$2") (pinfunction "2_P$2") (pintype "passive"))
      (node (ref "C15") (pin "P$2") (pinfunction "2_P$2") (pintype "passive"))
      (node (ref "C16") (pin "P$2") (pinfunction "2_P$2") (pintype "passive"))
      (node (ref "C17") (pin "P$2") (pinfunction "2_P$2") (pintype "passive"))
      (node (ref "C18") (pin "P$2") (pinfunction "2_P$2") (pintype "passive"))
      (node (ref "C19") (pin "P$1") (pinfunction "1_P$1") (pintype "passive"))
      (node (ref "C2") (pin "P$2") (pinfunction "2_P$2") (pintype "passive"))
      (node (ref "C20") (pin "P$1") (pinfunction "1_P$1") (pintype "passive"))
      (node (ref "C21") (pin "P$1") (pinfunction "1_P$1") (pintype "passive"))
      (node (ref "C22") (pin "P$1") (pinfunction "1_P$1") (pintype "passive"))
      (node (ref "C23") (pin "P$2") (pinfunction "2_P$2") (pintype "passive"))
      (node (ref "C24") (pin "P$1") (pinfunction "1_P$1") (pintype "passive"))
      (node (ref "C25") (pin "P$1") (pinfunction "1_P$1") (pintype "passive"))
      (node (ref "C26") (pin "P$2") (pinfunction "2_P$2") (pintype "passive"))
      (node (ref "C27") (pin "P$1") (pinfunction "1_P$1") (pintype "passive"))
      (node (ref "C28") (pin "P$2") (pinfunction "2_P$2") (pintype "passive"))
      (node (ref "C29") (pin "P$2") (pinfunction "2_P$2") (pintype "passive"))
      (node (ref "C3") (pin "P$2") (pinfunction "2_P$2") (pintype "passive"))
      (node (ref "C30") (pin "P$1") (pinfunction "1_P$1") (pintype "passive"))
      (node (ref "C31") (pin "2") (pinfunction "2_2") (pintype "passive"))
      (node (ref "C32") (pin "P$2") (pinfunction "2_P$2") (pintype "passive"))
      (node (ref "C33") (pin "P$2") (pinfunction "2_P$2") (pintype "passive"))
      (node (ref "C34") (pin "P$1") (pinfunction "1_P$1") (pintype "passive"))
      (node (ref "C35") (pin "P$1") (pinfunction "1_P$1") (pintype "passive"))
      (node (ref "C36") (pin "P$2") (pinfunction "2_P$2") (pintype "passive"))
      (node (ref "C37") (pin "P$2") (pinfunction "2_P$2") (pintype "passive"))
      (node (ref "C38") (pin "P$1") (pinfunction "1_P$1") (pintype "passive"))
      (node (ref "C39") (pin "P$2") (pinfunction "2_P$2") (pintype "passive"))
      (node (ref "C4") (pin "P$2") (pinfunction "2_P$2") (pintype "passive"))
      (node (ref "C40") (pin "P$2") (pinfunction "2_P$2") (pintype "passive"))
      (node (ref "C41") (pin "P$2") (pinfunction "2_P$2") (pintype "passive"))
      (node (ref "C42") (pin "P$2") (pinfunction "2_P$2") (pintype "passive"))
      (node (ref "C43") (pin "P$1") (pinfunction "1_P$1") (pintype "passive"))
      (node (ref "C5") (pin "P$2") (pinfunction "2_P$2") (pintype "passive"))
      (node (ref "C6") (pin "P$2") (pinfunction "2_P$2") (pintype "passive"))
      (node (ref "C7") (pin "P$2") (pinfunction "2_P$2") (pintype "passive"))
      (node (ref "C8") (pin "P$2") (pinfunction "2_P$2") (pintype "passive"))
      (node (ref "C9") (pin "P$2") (pinfunction "2_P$2") (pintype "passive"))
      (node (ref "J1") (pin "6") (pinfunction "SUPPLY_VOLTAGE_GROUND_6") (pintype "power_in"))
      (node (ref "J2") (pin "P$1") (pinfunction "P$1_P$1") (pintype "bidirectional"))
      (node (ref "J3") (pin "10") (pinfunction "10_10") (pintype "passive"))
      (node (ref "J3") (pin "6") (pinfunction "6_6") (pintype "passive"))
      (node (ref "J3") (pin "8") (pinfunction "8_8") (pintype "passive"))
      (node (ref "J6") (pin "GND") (pinfunction "GND_GND") (pintype "power_in"))
      (node (ref "J7") (pin "P$5") (pinfunction "GND_P$5") (pintype "bidirectional"))
      (node (ref "J8") (pin "P$1") (pinfunction "P$1_P$1") (pintype "bidirectional"))
      (node (ref "J9") (pin "10") (pinfunction "10_10") (pintype "passive"))
      (node (ref "J9") (pin "2") (pinfunction "2_2") (pintype "passive"))
      (node (ref "J9") (pin "4") (pinfunction "4_4") (pintype "passive"))
      (node (ref "J9") (pin "6") (pinfunction "6_6") (pintype "passive"))
      (node (ref "J9") (pin "8") (pinfunction "8_8") (pintype "passive"))
      (node (ref "LED1") (pin "2") (pinfunction "C_2") (pintype "passive"))
      (node (ref "R1") (pin "P$1") (pinfunction "1_P$1") (pintype "passive"))
      (node (ref "R21") (pin "P$1") (pinfunction "1_P$1") (pintype "passive"))
      (node (ref "R22") (pin "P$1") (pinfunction "1_P$1") (pintype "passive"))
      (node (ref "R23") (pin "P$1") (pinfunction "1_P$1") (pintype "passive"))
      (node (ref "R24") (pin "P$1") (pinfunction "1_P$1") (pintype "passive"))
      (node (ref "RJ1") (pin "10") (pinfunction "GLO_10") (pintype "bidirectional"))
      (node (ref "RJ1") (pin "8") (pinfunction "P8_8") (pintype "bidirectional"))
      (node (ref "U1") (pin "22") (pinfunction "GND_22") (pintype "power_in"))
      (node (ref "U1") (pin "25") (pinfunction "25_25") (pintype "passive"))
      (node (ref "U2") (pin "2") (pinfunction "GND_2") (pintype "input"))
      (node (ref "U3") (pin "111") (pinfunction "VSS(IO)5_111") (pintype "bidirectional"))
      (node (ref "U3") (pin "124") (pinfunction "VSS(IO)6_124") (pintype "bidirectional"))
      (node (ref "U3") (pin "139") (pinfunction "VSS(IO)7_139") (pintype "bidirectional"))
      (node (ref "U3") (pin "150") (pinfunction "VSS(IO)8_150") (pintype "bidirectional"))
      (node (ref "U3") (pin "153") (pinfunction "VREFL_153") (pintype "bidirectional"))
      (node (ref "U3") (pin "156") (pinfunction "AVSS0_156") (pintype "bidirectional"))
      (node (ref "U3") (pin "157") (pinfunction "VREFL0_157") (pintype "bidirectional"))
      (node (ref "U3") (pin "170") (pinfunction "VSS(IO)9_170") (pintype "bidirectional"))
      (node (ref "U3") (pin "22") (pinfunction "VSS1_22") (pintype "bidirectional"))
      (node (ref "U3") (pin "28") (pinfunction "AVSS_USBHS_28") (pintype "bidirectional"))
      (node (ref "U3") (pin "29") (pinfunction "PVSS_USBHS_29") (pintype "bidirectional"))
      (node (ref "U3") (pin "30") (pinfunction "VSS2_USBHS_30") (pintype "bidirectional"))
      (node (ref "U3") (pin "33") (pinfunction "VSS1_USBHS_33") (pintype "bidirectional"))
      (node (ref "U3") (pin "35") (pinfunction "VSSIO_35") (pintype "bidirectional"))
      (node (ref "U3") (pin "45") (pinfunction "VSS_USB_45") (pintype "bidirectional"))
      (node (ref "U3") (pin "60") (pinfunction "VSS(IO)2_60") (pintype "bidirectional"))
      (node (ref "U3") (pin "63") (pinfunction "VSS(IO/DCDC)_63") (pintype "bidirectional"))
      (node (ref "U3") (pin "66") (pinfunction "VCC_DCDC(IO/DCDC)_66") (pintype "bidirectional"))
      (node (ref "U3") (pin "83") (pinfunction "VSS(IO)3_83") (pintype "bidirectional"))
      (node (ref "U3") (pin "98") (pinfunction "VSS(IO)4_98") (pintype "bidirectional"))
      (node (ref "X1") (pin "2") (pinfunction "2_2") (pintype "bidirectional"))
      (node (ref "X1") (pin "4") (pinfunction "4_4") (pintype "bidirectional"))
      (node (ref "X2") (pin "2") (pinfunction "2_2") (pintype "bidirectional"))
      (node (ref "X2") (pin "4") (pinfunction "4_4") (pintype "bidirectional"))
    )
    (net (code "17") (name "GNDE") (class "Default")
      (node (ref "J1") (pin "S1") (pinfunction "SHIELD_S1") (pintype "passive"))
      (node (ref "J1") (pin "S2") (pinfunction "SHIELD_S2") (pintype "passive"))
      (node (ref "J1") (pin "S3") (pinfunction "SHIELD_S3") (pintype "passive"))
      (node (ref "J1") (pin "S4") (pinfunction "SHIELD_S4") (pintype "passive"))
      (node (ref "J2") (pin "P$4") (pinfunction "P$4_P$4") (pintype "bidirectional"))
      (node (ref "J6") (pin "SHLD1") (pinfunction "SHIELD_1_SHLD1") (pintype "bidirectional"))
      (node (ref "J6") (pin "SHLD2") (pinfunction "SHIELD_2_SHLD2") (pintype "bidirectional"))
      (node (ref "J7") (pin "P$6") (pinfunction "SHIELD1_P$6") (pintype "bidirectional"))
      (node (ref "J7") (pin "P$7") (pinfunction "SHIELD2_P$7") (pintype "bidirectional"))
      (node (ref "J7") (pin "P$8") (pinfunction "SHIELD3_P$8") (pintype "bidirectional"))
      (node (ref "J7") (pin "P$9") (pinfunction "SHIELD4_P$9") (pintype "bidirectional"))
      (node (ref "RJ1") (pin "13") (pinfunction "GNDE0_13") (pintype "bidirectional"))
      (node (ref "RJ1") (pin "14") (pinfunction "GNDE1_14") (pintype "bidirectional"))
    )
    (net (code "18") (name "ID") (class "Default")
      (node (ref "J7") (pin "P$4") (pinfunction "ID_P$4") (pintype "bidirectional"))
    )
    (net (code "19") (name "IIC_1_SCL") (class "Default")
      (node (ref "J8") (pin "P$5") (pinfunction "P$5_P$5") (pintype "bidirectional"))
      (node (ref "R14") (pin "P$2") (pinfunction "2_P$2") (pintype "passive"))
      (node (ref "U3") (pin "132") (pinfunction "P1_0_132") (pintype "bidirectional"))
    )
    (net (code "20") (name "IIC_1_SDA") (class "Default")
      (node (ref "J8") (pin "P$6") (pinfunction "P$6_P$6") (pintype "bidirectional"))
      (node (ref "R15") (pin "P$2") (pinfunction "2_P$2") (pintype "passive"))
      (node (ref "U3") (pin "131") (pinfunction "P1_1_131") (pintype "bidirectional"))
    )
    (net (code "21") (name "INT_MI_01") (class "Default")
      (node (ref "J8") (pin "P$39") (pinfunction "P$39_P$39") (pintype "bidirectional"))
      (node (ref "U3") (pin "87") (pinfunction "P3_1_87") (pintype "bidirectional"))
    )
    (net (code "22") (name "INT_MI_02") (class "Default")
      (node (ref "J8") (pin "P$40") (pinfunction "P$40_P$40") (pintype "bidirectional"))
      (node (ref "U3") (pin "86") (pinfunction "P3_2_86") (pintype "bidirectional"))
    )
    (net (code "23") (name "INT_MI_03") (class "Default")
      (node (ref "J8") (pin "P$9") (pinfunction "P$9_P$9") (pintype "bidirectional"))
      (node (ref "U3") (pin "128") (pinfunction "P1_4_128") (pintype "bidirectional"))
    )
    (net (code "24") (name "INT_MI_04") (class "Default")
      (node (ref "J8") (pin "P$10") (pinfunction "P$10_P$10") (pintype "bidirectional"))
      (node (ref "U3") (pin "127") (pinfunction "P1_5_127") (pintype "bidirectional"))
    )
    (net (code "25") (name "LED1{slash}SPEED") (class "Default")
      (node (ref "RJ1") (pin "11") (pinfunction "YLO_11") (pintype "bidirectional"))
      (node (ref "U1") (pin "23") (pinfunction "LED0/ANEN_SPEED_23") (pintype "bidirectional"))
    )
    (net (code "26") (name "NC") (class "Default")
      (node (ref "RJ1") (pin "7") (pinfunction "P7_7") (pintype "bidirectional"))
    )
    (net (code "27") (name "Net-(C8-1)") (class "Default")
      (node (ref "C8") (pin "P$1") (pinfunction "1_P$1") (pintype "passive"))
      (node (ref "C9") (pin "P$1") (pinfunction "1_P$1") (pintype "passive"))
      (node (ref "FB1") (pin "2") (pinfunction "P$2_2") (pintype "bidirectional"))
      (node (ref "U1") (pin "2") (pinfunction "VDDA_3.3_2") (pintype "power_in"))
    )
    (net (code "28") (name "Net-(C24-2)") (class "Default")
      (node (ref "C24") (pin "P$2") (pinfunction "2_P$2") (pintype "passive"))
      (node (ref "U3") (pin "148") (pinfunction "VCL2_148") (pintype "bidirectional"))
    )
    (net (code "29") (name "Net-(C28-1)") (class "Default")
      (node (ref "C28") (pin "P$1") (pinfunction "1_P$1") (pintype "passive"))
      (node (ref "J7") (pin "P$1") (pinfunction "VBUS_P$1") (pintype "bidirectional"))
      (node (ref "R16") (pin "P$2") (pinfunction "2_P$2") (pintype "passive"))
      (node (ref "R21") (pin "P$2") (pinfunction "2_P$2") (pintype "passive"))
    )
    (net (code "30") (name "Net-(C33-1)") (class "Default")
      (node (ref "C33") (pin "P$1") (pinfunction "1_P$1") (pintype "passive"))
      (node (ref "U3") (pin "19") (pinfunction "VCLO_19") (pintype "bidirectional"))
    )
    (net (code "31") (name "Net-(C42-1)") (class "Default")
      (node (ref "C42") (pin "P$1") (pinfunction "1_P$1") (pintype "passive"))
      (node (ref "U3") (pin "62") (pinfunction "VCL1_62") (pintype "bidirectional"))
    )
    (net (code "32") (name "Net-(J7-D+)") (class "Default")
      (node (ref "J7") (pin "P$3") (pinfunction "D+_P$3") (pintype "bidirectional"))
      (node (ref "R18") (pin "P$2") (pinfunction "2_P$2") (pintype "passive"))
    )
    (net (code "33") (name "Net-(J7-D-)") (class "Default")
      (node (ref "J7") (pin "P$2") (pinfunction "D-_P$2") (pintype "bidirectional"))
      (node (ref "R17") (pin "P$2") (pinfunction "2_P$2") (pintype "passive"))
    )
    (net (code "34") (name "Net-(LED1-A)") (class "Default")
      (node (ref "LED1") (pin "1") (pinfunction "A_1") (pintype "passive"))
      (node (ref "R5") (pin "P$1") (pinfunction "1_P$1") (pintype "passive"))
    )
    (net (code "35") (name "Net-(R22-2)") (class "Default")
      (node (ref "R22") (pin "P$2") (pinfunction "2_P$2") (pintype "passive"))
      (node (ref "U3") (pin "27") (pinfunction "USBHS_RREF_27") (pintype "bidirectional"))
    )
    (net (code "36") (name "Net-(R23-2)") (class "Default")
      (node (ref "R23") (pin "P$2") (pinfunction "2_P$2") (pintype "passive"))
      (node (ref "U3") (pin "64") (pinfunction "VLO1(DCDC)_64") (pintype "bidirectional"))
    )
    (net (code "37") (name "Net-(R24-2)") (class "Default")
      (node (ref "R24") (pin "P$2") (pinfunction "2_P$2") (pintype "passive"))
      (node (ref "U3") (pin "65") (pinfunction "VLO2(DCDC)_65") (pintype "bidirectional"))
    )
    (net (code "38") (name "P0_00") (class "Default")
      (node (ref "J4") (pin "P$2") (pinfunction "P$2_P$2") (pintype "bidirectional"))
      (node (ref "U3") (pin "169") (pinfunction "P0_0/AN0\\00_169") (pintype "bidirectional"))
    )
    (net (code "39") (name "P0_01") (class "Default")
      (node (ref "J4") (pin "P$1") (pinfunction "P$1_P$1") (pintype "bidirectional"))
      (node (ref "U3") (pin "168") (pinfunction "P0_1/AN001_168") (pintype "bidirectional"))
    )
    (net (code "40") (name "P0_02") (class "Default")
      (node (ref "J5") (pin "1") (pinfunction "1_1") (pintype "passive"))
      (node (ref "U3") (pin "167") (pinfunction "P0_2/AN002_167") (pintype "bidirectional"))
    )
    (net (code "41") (name "P0_03") (class "Default")
      (node (ref "J5") (pin "3") (pinfunction "3_3") (pintype "passive"))
      (node (ref "U3") (pin "166") (pinfunction "P0_3/PGAVSS000_166") (pintype "bidirectional"))
    )
    (net (code "42") (name "P0_04") (class "Default")
      (node (ref "J5") (pin "5") (pinfunction "5_5") (pintype "passive"))
      (node (ref "U3") (pin "165") (pinfunction "P0_4/AN100_165") (pintype "bidirectional"))
    )
    (net (code "43") (name "P0_05") (class "Default")
      (node (ref "J5") (pin "7") (pinfunction "7_7") (pintype "passive"))
      (node (ref "U3") (pin "164") (pinfunction "P0_5/AN101_164") (pintype "bidirectional"))
    )
    (net (code "44") (name "P0_06") (class "Default")
      (node (ref "J5") (pin "9") (pinfunction "9_9") (pintype "passive"))
      (node (ref "U3") (pin "163") (pinfunction "P0_6/AN102_163") (pintype "bidirectional"))
    )
    (net (code "45") (name "P0_07") (class "Default")
      (node (ref "J5") (pin "10") (pinfunction "10_10") (pintype "passive"))
      (node (ref "U3") (pin "162") (pinfunction "P0_7/PGVSS100_162") (pintype "bidirectional"))
    )
    (net (code "46") (name "P0_08") (class "Default")
      (node (ref "J5") (pin "8") (pinfunction "8_8") (pintype "passive"))
      (node (ref "U3") (pin "161") (pinfunction "P0_8/AN003_161") (pintype "bidirectional"))
    )
    (net (code "47") (name "P0_09") (class "Default")
      (node (ref "J5") (pin "6") (pinfunction "6_6") (pintype "passive"))
      (node (ref "U3") (pin "160") (pinfunction "P0_9/AN004_160") (pintype "bidirectional"))
    )
    (net (code "48") (name "P0_14") (class "Default")
      (node (ref "J5") (pin "4") (pinfunction "4_4") (pintype "passive"))
      (node (ref "U3") (pin "152") (pinfunction "P0_14/DA0/AN005/AN105_152") (pintype "bidirectional"))
    )
    (net (code "49") (name "P0_15") (class "Default")
      (node (ref "J5") (pin "2") (pinfunction "2_2") (pintype "passive"))
      (node (ref "U3") (pin "151") (pinfunction "P0_15/DA1/AN006/AN106_151") (pintype "bidirectional"))
    )
    (net (code "50") (name "P1_02") (class "Default")
      (node (ref "J8") (pin "P$7") (pinfunction "P$7_P$7") (pintype "bidirectional"))
      (node (ref "U3") (pin "130") (pinfunction "P1_2_130") (pintype "bidirectional"))
    )
    (net (code "51") (name "P1_03") (class "Default")
      (node (ref "J8") (pin "P$8") (pinfunction "P$8_P$8") (pintype "bidirectional"))
      (node (ref "U3") (pin "129") (pinfunction "P1_3_129") (pintype "bidirectional"))
    )
    (net (code "52") (name "P1_06") (class "Default")
      (node (ref "J8") (pin "P$11") (pinfunction "P$11_P$11") (pintype "bidirectional"))
      (node (ref "U3") (pin "126") (pinfunction "P1_6_126") (pintype "bidirectional"))
    )
    (net (code "53") (name "P1_07") (class "Default")
      (node (ref "J8") (pin "P$12") (pinfunction "P$12_P$12") (pintype "bidirectional"))
      (node (ref "U3") (pin "125") (pinfunction "P1_7_125") (pintype "bidirectional"))
    )
    (net (code "54") (name "P1_11") (class "Default")
      (node (ref "J8") (pin "P$38") (pinfunction "P$38_P$38") (pintype "bidirectional"))
      (node (ref "U3") (pin "92") (pinfunction "P1_11_92") (pintype "bidirectional"))
    )
    (net (code "55") (name "P1_12") (class "Default")
      (node (ref "J8") (pin "P$37") (pinfunction "P$37_P$37") (pintype "bidirectional"))
      (node (ref "U3") (pin "93") (pinfunction "P1_12_93") (pintype "bidirectional"))
    )
    (net (code "56") (name "P1_13") (class "Default")
      (node (ref "J8") (pin "P$36") (pinfunction "P$36_P$36") (pintype "bidirectional"))
      (node (ref "U3") (pin "94") (pinfunction "P1_13_94") (pintype "bidirectional"))
    )
    (net (code "57") (name "P1_14") (class "Default")
      (node (ref "J8") (pin "P$35") (pinfunction "P$35_P$35") (pintype "bidirectional"))
      (node (ref "U3") (pin "95") (pinfunction "P1_14_95") (pintype "bidirectional"))
    )
    (net (code "58") (name "P1_15") (class "Default")
      (node (ref "J8") (pin "P$34") (pinfunction "P$34_P$34") (pintype "bidirectional"))
      (node (ref "U3") (pin "96") (pinfunction "P1_15_96") (pintype "bidirectional"))
    )
    (net (code "59") (name "P2_00") (class "Default")
      (node (ref "J10") (pin "P$13") (pinfunction "P$13_P$13") (pintype "bidirectional"))
      (node (ref "U3") (pin "69") (pinfunction "P2_0(INPUT_ONLY)_69") (pintype "bidirectional"))
    )
    (net (code "60") (name "P2_01") (class "Default")
      (node (ref "J10") (pin "P$14") (pinfunction "P$14_P$14") (pintype "bidirectional"))
      (node (ref "U3") (pin "68") (pinfunction "P2_1/MD_68") (pintype "bidirectional"))
    )
    (net (code "61") (name "P2_02") (class "Default")
      (node (ref "J10") (pin "P$19") (pinfunction "P$19_P$19") (pintype "bidirectional"))
      (node (ref "U3") (pin "54") (pinfunction "P2_2_54") (pintype "bidirectional"))
    )
    (net (code "62") (name "P2_03") (class "Default")
      (node (ref "J9") (pin "1") (pinfunction "1_1") (pintype "passive"))
      (node (ref "U3") (pin "53") (pinfunction "P2_3_53") (pintype "bidirectional"))
    )
    (net (code "63") (name "P2_04") (class "Default")
      (node (ref "J9") (pin "3") (pinfunction "3_3") (pintype "passive"))
      (node (ref "U3") (pin "52") (pinfunction "P2_4_52") (pintype "bidirectional"))
    )
    (net (code "64") (name "P2_05") (class "Default")
      (node (ref "J9") (pin "5") (pinfunction "5_5") (pintype "passive"))
      (node (ref "U3") (pin "51") (pinfunction "P2_5_51") (pintype "bidirectional"))
    )
    (net (code "65") (name "P2_06") (class "Default")
      (node (ref "J9") (pin "7") (pinfunction "7_7") (pintype "passive"))
      (node (ref "U3") (pin "50") (pinfunction "P2_6_50") (pintype "bidirectional"))
    )
    (net (code "66") (name "P2_07") (class "Default")
      (node (ref "J9") (pin "9") (pinfunction "9_9") (pintype "passive"))
      (node (ref "U3") (pin "49") (pinfunction "P2_7_49") (pintype "bidirectional"))
    )
    (net (code "67") (name "P3_03") (class "Default")
      (node (ref "J10") (pin "P$2") (pinfunction "P$2_P$2") (pintype "bidirectional"))
      (node (ref "U3") (pin "85") (pinfunction "P3_3_85") (pintype "bidirectional"))
    )
    (net (code "68") (name "P3_04") (class "Default")
      (node (ref "J10") (pin "P$4") (pinfunction "P$4_P$4") (pintype "bidirectional"))
      (node (ref "U3") (pin "82") (pinfunction "P3_4_82") (pintype "bidirectional"))
    )
    (net (code "69") (name "P3_05") (class "Default")
      (node (ref "J10") (pin "P$6") (pinfunction "P$6_P$6") (pintype "bidirectional"))
      (node (ref "U3") (pin "81") (pinfunction "P3_5_81") (pintype "bidirectional"))
    )
    (net (code "70") (name "P3_06") (class "Default")
      (node (ref "J10") (pin "P$1") (pinfunction "P$1_P$1") (pintype "bidirectional"))
      (node (ref "U3") (pin "80") (pinfunction "P3_6_80") (pintype "bidirectional"))
    )
    (net (code "71") (name "P3_07") (class "Default")
      (node (ref "J10") (pin "P$3") (pinfunction "P$3_P$3") (pintype "bidirectional"))
      (node (ref "U3") (pin "79") (pinfunction "P3_7_79") (pintype "bidirectional"))
    )
    (net (code "72") (name "P3_09") (class "Default")
      (node (ref "J10") (pin "P$5") (pinfunction "P$5_P$5") (pintype "bidirectional"))
      (node (ref "U3") (pin "77") (pinfunction "P3_9_77") (pintype "bidirectional"))
    )
    (net (code "73") (name "P3_10") (class "Default")
      (node (ref "J10") (pin "P$7") (pinfunction "P$7_P$7") (pintype "bidirectional"))
      (node (ref "U3") (pin "76") (pinfunction "P3_10_76") (pintype "bidirectional"))
    )
    (net (code "74") (name "P3_11") (class "Default")
      (node (ref "J10") (pin "P$8") (pinfunction "P$8_P$8") (pintype "bidirectional"))
      (node (ref "U3") (pin "75") (pinfunction "P3_11_75") (pintype "bidirectional"))
    )
    (net (code "75") (name "P3_12") (class "Default")
      (node (ref "J10") (pin "P$9") (pinfunction "P$9_P$9") (pintype "bidirectional"))
      (node (ref "U3") (pin "74") (pinfunction "P3_12_74") (pintype "bidirectional"))
    )
    (net (code "76") (name "P3_13") (class "Default")
      (node (ref "J10") (pin "P$20") (pinfunction "P$20_P$20") (pintype "bidirectional"))
      (node (ref "U3") (pin "55") (pinfunction "P3_13_55") (pintype "bidirectional"))
    )
    (net (code "77") (name "P3_14") (class "Default")
      (node (ref "J10") (pin "P$17") (pinfunction "P$17_P$17") (pintype "bidirectional"))
      (node (ref "U3") (pin "56") (pinfunction "P3_14_56") (pintype "bidirectional"))
    )
    (net (code "78") (name "P3_15") (class "Default")
      (node (ref "J10") (pin "P$18") (pinfunction "P$18_P$18") (pintype "bidirectional"))
      (node (ref "U3") (pin "57") (pinfunction "P3_15_57") (pintype "bidirectional"))
    )
    (net (code "79") (name "P4_00") (class "Default")
      (node (ref "J4") (pin "P$7") (pinfunction "P$7_P$7") (pintype "bidirectional"))
      (node (ref "U3") (pin "1") (pinfunction "P4_0_1") (pintype "bidirectional"))
    )
    (net (code "80") (name "P4_01") (class "Default")
      (node (ref "J4") (pin "P$8") (pinfunction "P$8_P$8") (pintype "bidirectional"))
      (node (ref "U3") (pin "2") (pinfunction "P4_1_2") (pintype "bidirectional"))
    )
    (net (code "81") (name "P4_02") (class "Default")
      (node (ref "J4") (pin "P$9") (pinfunction "P$9_P$9") (pintype "bidirectional"))
      (node (ref "U3") (pin "3") (pinfunction "P4_2_3") (pintype "bidirectional"))
    )
    (net (code "82") (name "P4_08") (class "Default")
      (node (ref "J4") (pin "P$20") (pinfunction "P$20_P$20") (pintype "bidirectional"))
      (node (ref "U3") (pin "43") (pinfunction "P4_8_43") (pintype "bidirectional"))
    )
    (net (code "83") (name "P4_09") (class "Default")
      (node (ref "J4") (pin "P$19") (pinfunction "P$19_P$19") (pintype "bidirectional"))
      (node (ref "U3") (pin "42") (pinfunction "P4_9_42") (pintype "bidirectional"))
    )
    (net (code "84") (name "P4_10") (class "Default")
      (node (ref "J4") (pin "P$18") (pinfunction "P$18_P$18") (pintype "bidirectional"))
      (node (ref "U3") (pin "41") (pinfunction "P4_10_41") (pintype "bidirectional"))
    )
    (net (code "85") (name "P4_11") (class "Default")
      (node (ref "J4") (pin "P$17") (pinfunction "P$17_P$17") (pintype "bidirectional"))
      (node (ref "U3") (pin "40") (pinfunction "P4_11_40") (pintype "bidirectional"))
    )
    (net (code "86") (name "P4_12") (class "Default")
      (node (ref "J4") (pin "P$16") (pinfunction "P$16_P$16") (pintype "bidirectional"))
      (node (ref "U3") (pin "39") (pinfunction "P4_12_39") (pintype "bidirectional"))
    )
    (net (code "87") (name "P4_13") (class "Default")
      (node (ref "J4") (pin "P$15") (pinfunction "P$15_P$15") (pintype "bidirectional"))
      (node (ref "U3") (pin "38") (pinfunction "P4_13_38") (pintype "bidirectional"))
    )
    (net (code "88") (name "P4_14") (class "Default")
      (node (ref "J4") (pin "P$14") (pinfunction "P$14_P$14") (pintype "bidirectional"))
      (node (ref "U3") (pin "37") (pinfunction "P4_14_37") (pintype "bidirectional"))
    )
    (net (code "89") (name "P4_15") (class "Default")
      (node (ref "J4") (pin "P$13") (pinfunction "P$13_P$13") (pintype "bidirectional"))
      (node (ref "U3") (pin "36") (pinfunction "P4_15_36") (pintype "bidirectional"))
    )
    (net (code "90") (name "P5_11") (class "Default")
      (node (ref "J4") (pin "P$6") (pinfunction "P$6_P$6") (pintype "bidirectional"))
      (node (ref "U3") (pin "176") (pinfunction "P5_11_176") (pintype "bidirectional"))
    )
    (net (code "91") (name "P5_12") (class "Default")
      (node (ref "J4") (pin "P$5") (pinfunction "P$5_P$5") (pintype "bidirectional"))
      (node (ref "U3") (pin "175") (pinfunction "P5_12_175") (pintype "bidirectional"))
    )
    (net (code "92") (name "P5_13") (class "Default")
      (node (ref "J4") (pin "P$4") (pinfunction "P$4_P$4") (pintype "bidirectional"))
      (node (ref "U3") (pin "174") (pinfunction "P5_13_174") (pintype "bidirectional"))
    )
    (net (code "93") (name "P6_00") (class "Default")
      (node (ref "J8") (pin "P$13") (pinfunction "P$13_P$13") (pintype "bidirectional"))
      (node (ref "U3") (pin "122") (pinfunction "P6_0_122") (pintype "bidirectional"))
    )
    (net (code "94") (name "P6_01") (class "Default")
      (node (ref "J8") (pin "P$14") (pinfunction "P$14_P$14") (pintype "bidirectional"))
      (node (ref "U3") (pin "121") (pinfunction "P6_1_121") (pintype "bidirectional"))
    )
    (net (code "95") (name "P6_02") (class "Default")
      (node (ref "J8") (pin "P$15") (pinfunction "P$15_P$15") (pintype "bidirectional"))
      (node (ref "U3") (pin "120") (pinfunction "P6_2_120") (pintype "bidirectional"))
    )
    (net (code "96") (name "P6_03") (class "Default")
      (node (ref "J8") (pin "P$16") (pinfunction "P$16_P$16") (pintype "bidirectional"))
      (node (ref "U3") (pin "119") (pinfunction "P6_3_119") (pintype "bidirectional"))
    )
    (net (code "97") (name "P6_04") (class "Default")
      (node (ref "J8") (pin "P$17") (pinfunction "P$17_P$17") (pintype "bidirectional"))
      (node (ref "U3") (pin "118") (pinfunction "P6_4_118") (pintype "bidirectional"))
    )
    (net (code "98") (name "P6_05") (class "Default")
      (node (ref "J8") (pin "P$18") (pinfunction "P$18_P$18") (pintype "bidirectional"))
      (node (ref "U3") (pin "117") (pinfunction "P6_5_117") (pintype "bidirectional"))
    )
    (net (code "99") (name "P6_06") (class "Default")
      (node (ref "J8") (pin "P$19") (pinfunction "P$19_P$19") (pintype "bidirectional"))
      (node (ref "U3") (pin "116") (pinfunction "P6_6_116") (pintype "bidirectional"))
    )
    (net (code "100") (name "P6_07") (class "Default")
      (node (ref "J8") (pin "P$20") (pinfunction "P$20_P$20") (pintype "bidirectional"))
      (node (ref "U3") (pin "115") (pinfunction "P6_7_115") (pintype "bidirectional"))
    )
    (net (code "101") (name "P6_08") (class "Default")
      (node (ref "J8") (pin "P$33") (pinfunction "P$33_P$33") (pintype "bidirectional"))
      (node (ref "U3") (pin "99") (pinfunction "P6_8_99") (pintype "bidirectional"))
    )
    (net (code "102") (name "P6_09") (class "Default")
      (node (ref "J8") (pin "P$32") (pinfunction "P$32_P$32") (pintype "bidirectional"))
      (node (ref "U3") (pin "100") (pinfunction "P6_9_100") (pintype "bidirectional"))
    )
    (net (code "103") (name "P6_10") (class "Default")
      (node (ref "J8") (pin "P$31") (pinfunction "P$31_P$31") (pintype "bidirectional"))
      (node (ref "U3") (pin "101") (pinfunction "P6_10_101") (pintype "bidirectional"))
    )
    (net (code "104") (name "P6_11") (class "Default")
      (node (ref "J8") (pin "P$30") (pinfunction "P$30_P$30") (pintype "bidirectional"))
      (node (ref "U3") (pin "102") (pinfunction "P6_11_102") (pintype "bidirectional"))
    )
    (net (code "105") (name "P6_12") (class "Default")
      (node (ref "J8") (pin "P$29") (pinfunction "P$29_P$29") (pintype "bidirectional"))
      (node (ref "U3") (pin "103") (pinfunction "P6_12_103") (pintype "bidirectional"))
    )
    (net (code "106") (name "P6_13") (class "Default")
      (node (ref "J8") (pin "P$28") (pinfunction "P$28_P$28") (pintype "bidirectional"))
      (node (ref "U3") (pin "104") (pinfunction "P6_13_104") (pintype "bidirectional"))
    )
    (net (code "107") (name "P6_14") (class "Default")
      (node (ref "J8") (pin "P$27") (pinfunction "P$27_P$27") (pintype "bidirectional"))
      (node (ref "U3") (pin "105") (pinfunction "P6_14_105") (pintype "bidirectional"))
    )
    (net (code "108") (name "P6_15") (class "Default")
      (node (ref "J8") (pin "P$26") (pinfunction "P$26_P$26") (pintype "bidirectional"))
      (node (ref "U3") (pin "106") (pinfunction "P6_15_106") (pintype "bidirectional"))
    )
    (net (code "109") (name "P7_06") (class "Default")
      (node (ref "J4") (pin "P$10") (pinfunction "P$10_P$10") (pintype "bidirectional"))
      (node (ref "U3") (pin "14") (pinfunction "P7_6_14") (pintype "bidirectional"))
    )
    (net (code "110") (name "P7_07") (class "Default")
      (node (ref "J4") (pin "P$11") (pinfunction "P$11_P$11") (pintype "bidirectional"))
      (node (ref "U3") (pin "15") (pinfunction "P7_7_15") (pintype "bidirectional"))
    )
    (net (code "111") (name "P8_00") (class "Default")
      (node (ref "J8") (pin "P$4") (pinfunction "P$4_P$4") (pintype "bidirectional"))
      (node (ref "U3") (pin "133") (pinfunction "P8_0_133") (pintype "bidirectional"))
    )
    (net (code "112") (name "P8_01") (class "Default")
      (node (ref "J8") (pin "P$3") (pinfunction "P$3_P$3") (pintype "bidirectional"))
      (node (ref "U3") (pin "134") (pinfunction "P8_1_134") (pintype "bidirectional"))
    )
    (net (code "113") (name "P8_02") (class "Default")
      (node (ref "J8") (pin "P$2") (pinfunction "P$2_P$2") (pintype "bidirectional"))
      (node (ref "U3") (pin "135") (pinfunction "P8_2_135") (pintype "bidirectional"))
    )
    (net (code "114") (name "P8_03") (class "Default")
      (node (ref "U3") (pin "136") (pinfunction "P8_3_136") (pintype "bidirectional"))
    )
    (net (code "115") (name "P8_04") (class "Default")
      (node (ref "U3") (pin "137") (pinfunction "P8_4_137") (pintype "bidirectional"))
    )
    (net (code "116") (name "P8_05") (class "Default")
      (node (ref "J4") (pin "P$3") (pinfunction "P$3_P$3") (pintype "bidirectional"))
      (node (ref "U3") (pin "173") (pinfunction "P8_5_173") (pintype "bidirectional"))
    )
    (net (code "117") (name "P9_00") (class "Default")
      (node (ref "J10") (pin "P$16") (pinfunction "P$16_P$16") (pintype "bidirectional"))
      (node (ref "U3") (pin "58") (pinfunction "P9_0_58") (pintype "bidirectional"))
    )
    (net (code "118") (name "P9_01") (class "Default")
      (node (ref "J10") (pin "P$15") (pinfunction "P$15_P$15") (pintype "bidirectional"))
      (node (ref "U3") (pin "59") (pinfunction "P9_1_59") (pintype "bidirectional"))
    )
    (net (code "119") (name "P9_05") (class "Default")
      (node (ref "J10") (pin "P$10") (pinfunction "P$10_P$10") (pintype "bidirectional"))
      (node (ref "U3") (pin "73") (pinfunction "P9_5_73") (pintype "bidirectional"))
    )
    (net (code "120") (name "P9_06") (class "Default")
      (node (ref "J10") (pin "P$11") (pinfunction "P$11_P$11") (pintype "bidirectional"))
      (node (ref "U3") (pin "72") (pinfunction "P9_6_72") (pintype "bidirectional"))
    )
    (net (code "121") (name "P9_07") (class "Default")
      (node (ref "J10") (pin "P$12") (pinfunction "P$12_P$12") (pintype "bidirectional"))
      (node (ref "U3") (pin "71") (pinfunction "P9_7_71") (pintype "bidirectional"))
    )
    (net (code "122") (name "P9_08") (class "Default")
      (node (ref "U3") (pin "70") (pinfunction "P9_8_70") (pintype "bidirectional"))
    )
    (net (code "123") (name "PA_00") (class "Default")
      (node (ref "J8") (pin "P$21") (pinfunction "P$21_P$21") (pintype "bidirectional"))
      (node (ref "U3") (pin "114") (pinfunction "PA_0_114") (pintype "bidirectional"))
    )
    (net (code "124") (name "PA_01") (class "Default")
      (node (ref "J8") (pin "P$22") (pinfunction "P$22_P$22") (pintype "bidirectional"))
      (node (ref "U3") (pin "113") (pinfunction "PA_1_113") (pintype "bidirectional"))
    )
    (net (code "125") (name "PA_08") (class "Default")
      (node (ref "J8") (pin "P$25") (pinfunction "P$25_P$25") (pintype "bidirectional"))
      (node (ref "U3") (pin "107") (pinfunction "PA_8_107") (pintype "bidirectional"))
    )
    (net (code "126") (name "PA_09") (class "Default")
      (node (ref "J8") (pin "P$24") (pinfunction "P$24_P$24") (pintype "bidirectional"))
      (node (ref "U3") (pin "108") (pinfunction "PA_9_108") (pintype "bidirectional"))
    )
    (net (code "127") (name "PA_10") (class "Default")
      (node (ref "J8") (pin "P$23") (pinfunction "P$23_P$23") (pintype "bidirectional"))
      (node (ref "U3") (pin "109") (pinfunction "PA_10_109") (pintype "bidirectional"))
    )
    (net (code "128") (name "PB_00") (class "Default")
      (node (ref "J4") (pin "P$12") (pinfunction "P$12_P$12") (pintype "bidirectional"))
      (node (ref "U3") (pin "16") (pinfunction "PB_0_16") (pintype "bidirectional"))
    )
    (net (code "129") (name "R51") (class "Default")
      (node (ref "R7") (pin "P$1") (pinfunction "1_P$1") (pintype "passive"))
      (node (ref "RJ1") (pin "12") (pinfunction "YHI_12") (pintype "bidirectional"))
    )
    (net (code "130") (name "R52") (class "Default")
      (node (ref "R8") (pin "P$1") (pinfunction "1_P$1") (pintype "passive"))
      (node (ref "RJ1") (pin "9") (pinfunction "GHI_9") (pintype "bidirectional"))
    )
    (net (code "131") (name "RESET") (class "Default")
      (node (ref "C16") (pin "P$1") (pinfunction "1_P$1") (pintype "passive"))
      (node (ref "J3") (pin "9") (pinfunction "9_9") (pintype "passive"))
      (node (ref "R13") (pin "P$1") (pinfunction "1_P$1") (pintype "passive"))
      (node (ref "U3") (pin "67") (pinfunction "RES#_67") (pintype "bidirectional"))
    )
    (net (code "132") (name "REXT") (class "Default")
      (node (ref "C3") (pin "P$1") (pinfunction "1_P$1") (pintype "passive"))
      (node (ref "R1") (pin "P$2") (pinfunction "2_P$2") (pintype "passive"))
      (node (ref "U1") (pin "9") (pinfunction "REXT_9") (pintype "input"))
    )
    (net (code "133") (name "RXD0") (class "Default")
      (node (ref "R10") (pin "P$2") (pinfunction "2_P$2") (pintype "passive"))
      (node (ref "U1") (pin "13") (pinfunction "RXD0_13") (pintype "bidirectional"))
    )
    (net (code "134") (name "RXD1") (class "Default")
      (node (ref "R9") (pin "P$2") (pinfunction "2_P$2") (pintype "passive"))
      (node (ref "U1") (pin "12") (pinfunction "RXD1_12") (pintype "bidirectional"))
    )
    (net (code "135") (name "RXER") (class "Default")
      (node (ref "R11") (pin "P$2") (pinfunction "2_P$2") (pintype "passive"))
      (node (ref "U1") (pin "17") (pinfunction "RXER_17") (pintype "bidirectional"))
    )
    (net (code "136") (name "RXM") (class "Default")
      (node (ref "RJ1") (pin "6") (pinfunction "RD-_6") (pintype "bidirectional"))
      (node (ref "U1") (pin "3") (pinfunction "RXM_3") (pintype "bidirectional"))
    )
    (net (code "137") (name "RXP") (class "Default")
      (node (ref "RJ1") (pin "3") (pinfunction "RD+_3") (pintype "bidirectional"))
      (node (ref "U1") (pin "4") (pinfunction "RXP_4") (pintype "bidirectional"))
    )
    (net (code "138") (name "SD1_CD") (class "Default")
      (node (ref "J1") (pin "10") (pinfunction "CD_SWITCH2_10") (pintype "bidirectional"))
      (node (ref "U3") (pin "146") (pinfunction "P5_6/AN019_146") (pintype "bidirectional"))
    )
    (net (code "139") (name "SD1_CLK") (class "Default")
      (node (ref "J1") (pin "5") (pinfunction "CLOCK_5") (pintype "bidirectional"))
      (node (ref "U3") (pin "140") (pinfunction "P5_0/AN016_140") (pintype "bidirectional"))
    )
    (net (code "140") (name "SD1_CMD") (class "Default")
      (node (ref "J1") (pin "3") (pinfunction "COMMAND/RESPONSE_3") (pintype "bidirectional"))
      (node (ref "U3") (pin "141") (pinfunction "P5_1/AN116_141") (pintype "bidirectional"))
    )
    (net (code "141") (name "SD1_DAT0") (class "Default")
      (node (ref "J1") (pin "7") (pinfunction "DATA_LINE[BIT_0]_7") (pintype "bidirectional"))
      (node (ref "U3") (pin "142") (pinfunction "P5_2/AN017_142") (pintype "bidirectional"))
    )
    (net (code "142") (name "SD1_DAT1") (class "Default")
      (node (ref "J1") (pin "8") (pinfunction "DATA_LINE[BIT_1]_8") (pintype "bidirectional"))
      (node (ref "U3") (pin "143") (pinfunction "P5_3/AN117_143") (pintype "bidirectional"))
    )
    (net (code "143") (name "SD1_DAT2") (class "Default")
      (node (ref "J1") (pin "1") (pinfunction "DATA_LINE[BIT_2]_1") (pintype "bidirectional"))
      (node (ref "U3") (pin "144") (pinfunction "P5_4/AN018_144") (pintype "bidirectional"))
    )
    (net (code "144") (name "SD1_DAT3") (class "Default")
      (node (ref "J1") (pin "2") (pinfunction "CARD_DETECT/DATA_LINE[BIT_3]_2") (pintype "bidirectional"))
      (node (ref "U3") (pin "145") (pinfunction "P5_5/AN118_145") (pintype "bidirectional"))
    )
    (net (code "145") (name "SD1_WP") (class "Default")
      (node (ref "J1") (pin "9") (pinfunction "CD_SWITCH1_9") (pintype "bidirectional"))
      (node (ref "U3") (pin "147") (pinfunction "P5_7/AN119_147") (pintype "bidirectional"))
    )
    (net (code "146") (name "TCK") (class "Default")
      (node (ref "J3") (pin "7") (pinfunction "7_7") (pintype "passive"))
      (node (ref "U3") (pin "88") (pinfunction "P3_0_88") (pintype "bidirectional"))
    )
    (net (code "147") (name "TDI") (class "Default")
      (node (ref "J3") (pin "1") (pinfunction "1_1") (pintype "passive"))
      (node (ref "U3") (pin "91") (pinfunction "P1_10_91") (pintype "bidirectional"))
    )
    (net (code "148") (name "TDO") (class "Default")
      (node (ref "J3") (pin "3") (pinfunction "3_3") (pintype "passive"))
      (node (ref "U3") (pin "90") (pinfunction "P1_9_90") (pintype "bidirectional"))
    )
    (net (code "149") (name "TMS") (class "Default")
      (node (ref "J3") (pin "5") (pinfunction "5_5") (pintype "passive"))
      (node (ref "U3") (pin "89") (pinfunction "P1_8_89") (pintype "bidirectional"))
    )
    (net (code "150") (name "TXM") (class "Default")
      (node (ref "RJ1") (pin "2") (pinfunction "TD-_2") (pintype "bidirectional"))
      (node (ref "U1") (pin "5") (pinfunction "TXM_5") (pintype "bidirectional"))
    )
    (net (code "151") (name "TXP") (class "Default")
      (node (ref "RJ1") (pin "1") (pinfunction "TD+_1") (pintype "bidirectional"))
      (node (ref "U1") (pin "6") (pinfunction "TXP_6") (pintype "bidirectional"))
    )
    (net (code "152") (name "USBHS_FAULT") (class "Default")
      (node (ref "R19") (pin "P$1") (pinfunction "1_P$1") (pintype "passive"))
      (node (ref "U2") (pin "3") (pinfunction "FLG_3") (pintype "input"))
      (node (ref "U3") (pin "78") (pinfunction "P3_8_78") (pintype "bidirectional"))
    )
    (net (code "153") (name "USBHS_N") (class "Default")
      (node (ref "J6") (pin "D-") (pinfunction "D-_D-") (pintype "bidirectional"))
      (node (ref "U3") (pin "31") (pinfunction "USBHS_DM_31") (pintype "bidirectional"))
    )
    (net (code "154") (name "USBHS_P") (class "Default")
      (node (ref "J6") (pin "D+") (pinfunction "D+_D+") (pintype "bidirectional"))
      (node (ref "U3") (pin "32") (pinfunction "USBHS_DP_32") (pintype "bidirectional"))
    )
    (net (code "155") (name "USBHS_VBUS") (class "Default")
      (node (ref "C29") (pin "P$1") (pinfunction "1_P$1") (pintype "passive"))
      (node (ref "C31") (pin "1") (pinfunction "1_1") (pintype "passive"))
      (node (ref "J6") (pin "VBUS") (pinfunction "VBUS_VBUS") (pintype "power_in"))
      (node (ref "U2") (pin "5") (pinfunction "OUT_5") (pintype "input"))
      (node (ref "U3") (pin "17") (pinfunction "PB_1_17") (pintype "bidirectional"))
    )
    (net (code "156") (name "USBHS_VBUSEN") (class "Default")
      (node (ref "R20") (pin "P$1") (pinfunction "1_P$1") (pintype "passive"))
      (node (ref "U2") (pin "1") (pinfunction "EN_1") (pintype "input"))
    )
    (net (code "157") (name "USB_N") (class "Default")
      (node (ref "R17") (pin "P$1") (pinfunction "1_P$1") (pintype "passive"))
      (node (ref "U3") (pin "46") (pinfunction "USB_DM_46") (pintype "bidirectional"))
    )
    (net (code "158") (name "USB_P") (class "Default")
      (node (ref "R18") (pin "P$1") (pinfunction "1_P$1") (pintype "passive"))
      (node (ref "U3") (pin "47") (pinfunction "USB_DP_47") (pintype "bidirectional"))
    )
    (net (code "159") (name "USB_VBUS_B") (class "Default")
      (node (ref "R16") (pin "P$1") (pinfunction "1_P$1") (pintype "passive"))
      (node (ref "U3") (pin "44") (pinfunction "P4_7_44") (pintype "bidirectional"))
    )
    (net (code "160") (name "VCL_F(FLASH)") (class "Default")
      (node (ref "C34") (pin "P$2") (pinfunction "2_P$2") (pintype "passive"))
      (node (ref "U3") (pin "112") (pinfunction "VCL_F(FLASH)_112") (pintype "bidirectional"))
    )
    (net (code "161") (name "VDD") (class "Default")
      (node (ref "C14") (pin "P$1") (pinfunction "1_P$1") (pintype "passive"))
      (node (ref "C15") (pin "P$1") (pinfunction "1_P$1") (pintype "passive"))
      (node (ref "C19") (pin "P$2") (pinfunction "2_P$2") (pintype "passive"))
      (node (ref "C20") (pin "P$2") (pinfunction "2_P$2") (pintype "passive"))
      (node (ref "C21") (pin "P$2") (pinfunction "2_P$2") (pintype "passive"))
      (node (ref "C22") (pin "P$2") (pinfunction "2_P$2") (pintype "passive"))
      (node (ref "C25") (pin "P$2") (pinfunction "2_P$2") (pintype "passive"))
      (node (ref "C27") (pin "P$2") (pinfunction "2_P$2") (pintype "passive"))
      (node (ref "C30") (pin "P$2") (pinfunction "2_P$2") (pintype "passive"))
      (node (ref "C35") (pin "P$2") (pinfunction "2_P$2") (pintype "passive"))
      (node (ref "C36") (pin "P$1") (pinfunction "1_P$1") (pintype "passive"))
      (node (ref "C38") (pin "P$2") (pinfunction "2_P$2") (pintype "passive"))
      (node (ref "C39") (pin "P$1") (pinfunction "1_P$1") (pintype "passive"))
      (node (ref "C4") (pin "P$1") (pinfunction "1_P$1") (pintype "passive"))
      (node (ref "C40") (pin "P$1") (pinfunction "1_P$1") (pintype "passive"))
      (node (ref "C41") (pin "P$1") (pinfunction "1_P$1") (pintype "passive"))
      (node (ref "C43") (pin "P$2") (pinfunction "2_P$2") (pintype "passive"))
      (node (ref "C5") (pin "P$1") (pinfunction "1_P$1") (pintype "passive"))
      (node (ref "C7") (pin "P$1") (pinfunction "1_P$1") (pintype "passive"))
      (node (ref "FB1") (pin "1") (pinfunction "P$1_1") (pintype "bidirectional"))
      (node (ref "J1") (pin "4") (pinfunction "SUPPLY_VOLTAGE_4") (pintype "power_in"))
      (node (ref "J3") (pin "2") (pinfunction "2_2") (pintype "passive"))
      (node (ref "J3") (pin "4") (pinfunction "4_4") (pintype "passive"))
      (node (ref "L1") (pin "2") (pinfunction "P$2_2") (pintype "bidirectional"))
      (node (ref "R13") (pin "P$2") (pinfunction "2_P$2") (pintype "passive"))
      (node (ref "R14") (pin "P$1") (pinfunction "1_P$1") (pintype "passive"))
      (node (ref "R15") (pin "P$1") (pinfunction "1_P$1") (pintype "passive"))
      (node (ref "R2") (pin "P$2") (pinfunction "2_P$2") (pintype "passive"))
      (node (ref "R3") (pin "P$2") (pinfunction "2_P$2") (pintype "passive"))
      (node (ref "R4") (pin "P$2") (pinfunction "2_P$2") (pintype "passive"))
      (node (ref "R5") (pin "P$2") (pinfunction "2_P$2") (pintype "passive"))
      (node (ref "R6") (pin "P$2") (pinfunction "2_P$2") (pintype "passive"))
      (node (ref "R7") (pin "P$2") (pinfunction "2_P$2") (pintype "passive"))
      (node (ref "R8") (pin "P$2") (pinfunction "2_P$2") (pintype "passive"))
      (node (ref "U1") (pin "14") (pinfunction "VDDIO_14") (pintype "power_in"))
      (node (ref "U3") (pin "110") (pinfunction "VCC(IO)5_110") (pintype "bidirectional"))
      (node (ref "U3") (pin "123") (pinfunction "VCC(IO)6_123") (pintype "bidirectional"))
      (node (ref "U3") (pin "138") (pinfunction "VCC(IO)7_138") (pintype "bidirectional"))
      (node (ref "U3") (pin "149") (pinfunction "VCC(IO)8_149") (pintype "bidirectional"))
      (node (ref "U3") (pin "154") (pinfunction "VREFH_154") (pintype "bidirectional"))
      (node (ref "U3") (pin "155") (pinfunction "AVCC0_155") (pintype "bidirectional"))
      (node (ref "U3") (pin "158") (pinfunction "VREFH0_158") (pintype "bidirectional"))
      (node (ref "U3") (pin "171") (pinfunction "VCC(IO)9_171") (pintype "bidirectional"))
      (node (ref "U3") (pin "25") (pinfunction "VCC1_25") (pintype "bidirectional"))
      (node (ref "U3") (pin "26") (pinfunction "AVCC_SUBHS_26") (pintype "bidirectional"))
      (node (ref "U3") (pin "34") (pinfunction "VCC_USBHS_34") (pintype "bidirectional"))
      (node (ref "U3") (pin "48") (pinfunction "VCC_USB_48") (pintype "bidirectional"))
      (node (ref "U3") (pin "61") (pinfunction "VCC(IO)2_61") (pintype "bidirectional"))
      (node (ref "U3") (pin "84") (pinfunction "VCC(IO)3_84") (pintype "bidirectional"))
      (node (ref "U3") (pin "97") (pinfunction "VCC(IO)4_97") (pintype "bidirectional"))
    )
    (net (code "162") (name "VDD5") (class "Default")
      (node (ref "C23") (pin "P$1") (pinfunction "1_P$1") (pintype "passive"))
      (node (ref "C26") (pin "P$1") (pinfunction "1_P$1") (pintype "passive"))
      (node (ref "J2") (pin "P$3") (pinfunction "P$3_P$3") (pintype "bidirectional"))
      (node (ref "R19") (pin "P$2") (pinfunction "2_P$2") (pintype "passive"))
      (node (ref "R20") (pin "P$2") (pinfunction "2_P$2") (pintype "passive"))
      (node (ref "U2") (pin "4") (pinfunction "VIN_4") (pintype "input"))
    )
    (net (code "163") (name "VDDIN") (class "Default")
      (node (ref "J2") (pin "P$2") (pinfunction "P$2_P$2") (pintype "bidirectional"))
      (node (ref "L1") (pin "1") (pinfunction "P$1_1") (pintype "bidirectional"))
    )
    (net (code "164") (name "VDD_1.2") (class "Default")
      (node (ref "C10") (pin "P$1") (pinfunction "1_P$1") (pintype "passive"))
      (node (ref "C11") (pin "P$1") (pinfunction "1_P$1") (pintype "passive"))
      (node (ref "U1") (pin "1") (pinfunction "VDD_1.2_1") (pintype "power_in"))
    )
    (net (code "165") (name "XCIN") (class "Default")
      (node (ref "C32") (pin "P$1") (pinfunction "1_P$1") (pintype "passive"))
      (node (ref "U3") (pin "20") (pinfunction "XCIN_20") (pintype "bidirectional"))
      (node (ref "X3") (pin "P$1") (pinfunction "P$1_P$1") (pintype "bidirectional"))
    )
    (net (code "166") (name "XCOUT") (class "Default")
      (node (ref "C37") (pin "P$1") (pinfunction "1_P$1") (pintype "passive"))
      (node (ref "U3") (pin "21") (pinfunction "XCOUT_21") (pintype "bidirectional"))
      (node (ref "X3") (pin "P$2") (pinfunction "P$2_P$2") (pintype "bidirectional"))
    )
    (net (code "167") (name "XII") (class "Default")
      (node (ref "C1") (pin "P$1") (pinfunction "1_P$1") (pintype "passive"))
      (node (ref "U1") (pin "8") (pinfunction "XI_8") (pintype "input"))
      (node (ref "X1") (pin "1") (pinfunction "1_1") (pintype "bidirectional"))
    )
    (net (code "168") (name "XOO") (class "Default")
      (node (ref "C2") (pin "P$1") (pinfunction "1_P$1") (pintype "passive"))
      (node (ref "U1") (pin "7") (pinfunction "XO_7") (pintype "output"))
      (node (ref "X1") (pin "3") (pinfunction "3_3") (pintype "bidirectional"))
    )
    (net (code "169") (name "XTAL1") (class "Default")
      (node (ref "C17") (pin "P$1") (pinfunction "1_P$1") (pintype "passive"))
      (node (ref "U3") (pin "23") (pinfunction "P2_13/XTAL_23") (pintype "bidirectional"))
      (node (ref "X2") (pin "1") (pinfunction "1_1") (pintype "bidirectional"))
    )
    (net (code "170") (name "XTAL2") (class "Default")
      (node (ref "C18") (pin "P$1") (pinfunction "1_P$1") (pintype "passive"))
      (node (ref "U3") (pin "24") (pinfunction "P2_12/EXTAL_24") (pintype "bidirectional"))
      (node (ref "X2") (pin "3") (pinfunction "3_3") (pintype "bidirectional"))
    )
    (net (code "171") (name "unconnected-(U3-VBAT-Pad18)") (class "Default")
      (node (ref "U3") (pin "18") (pinfunction "VBAT_18") (pintype "bidirectional"))
    )
  )
)
